# StairLed.net
KiCad netlist of a schematic drawn in Altium Designer
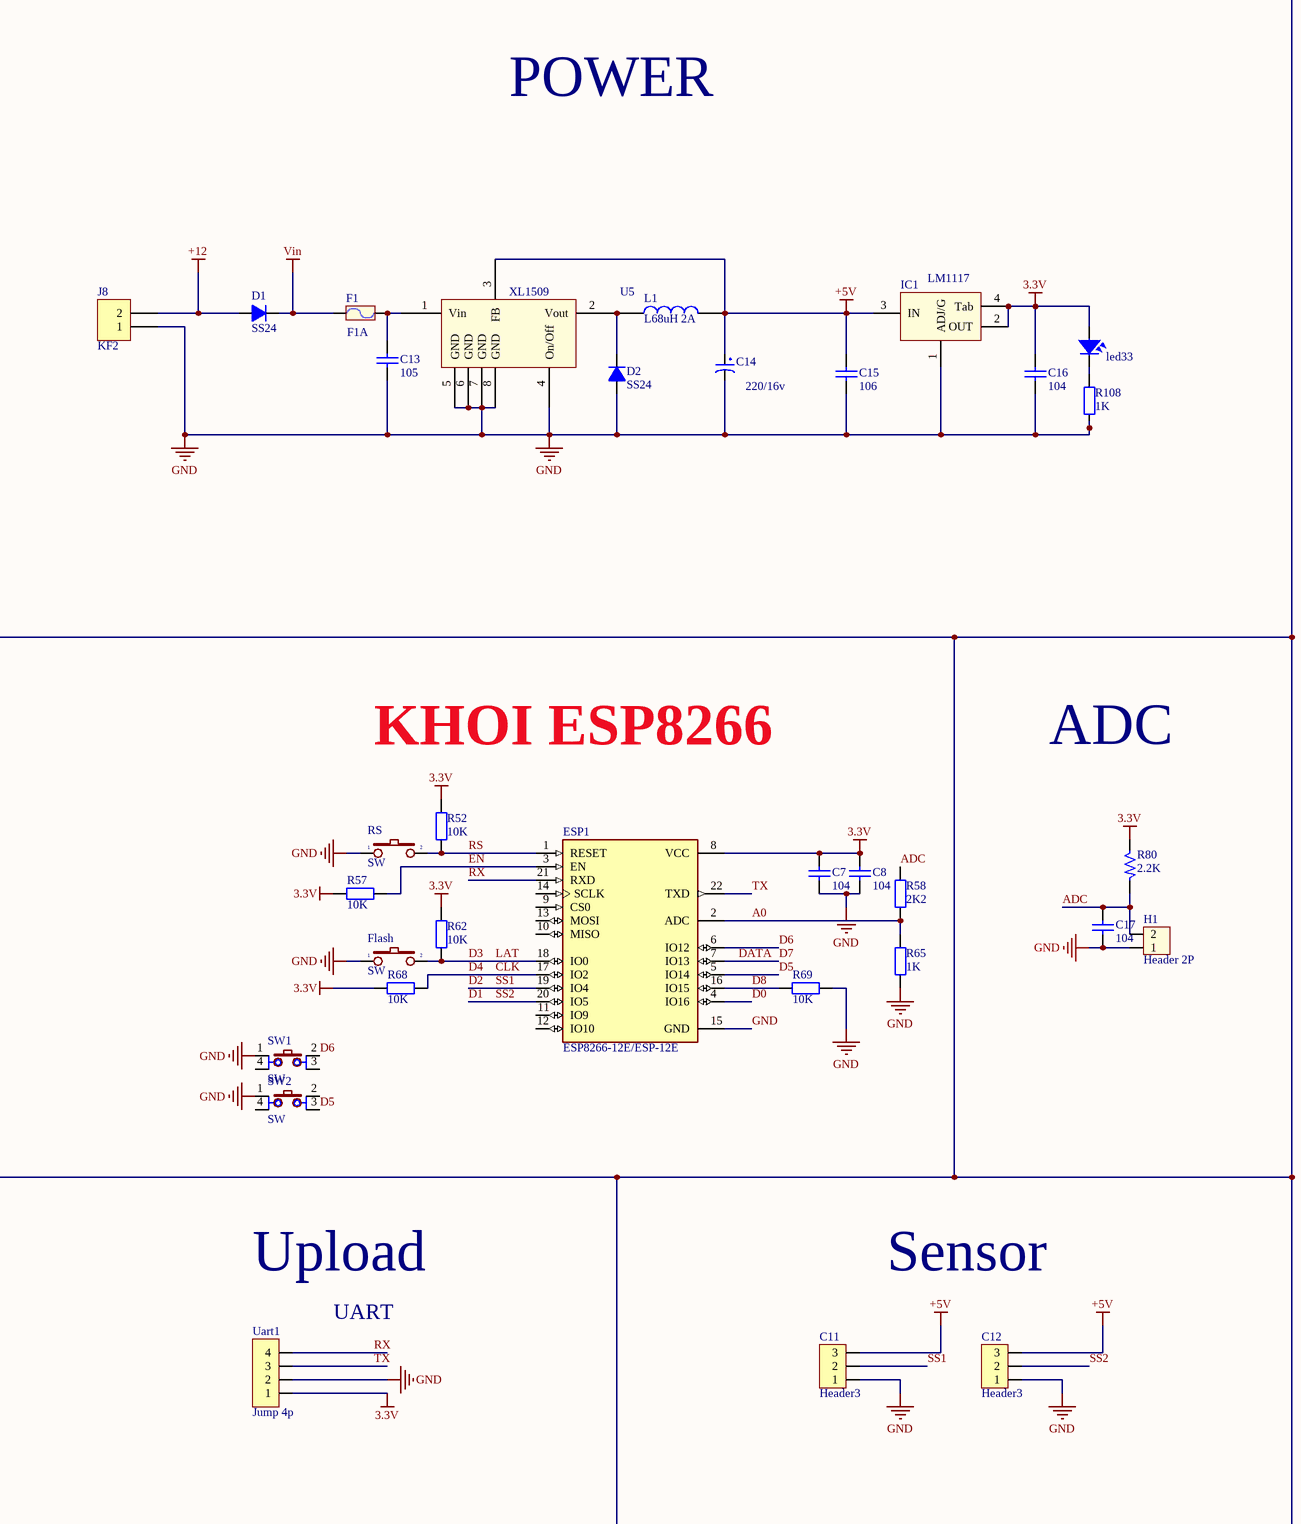
[diagram p0: StairLed.SchDoc, left]
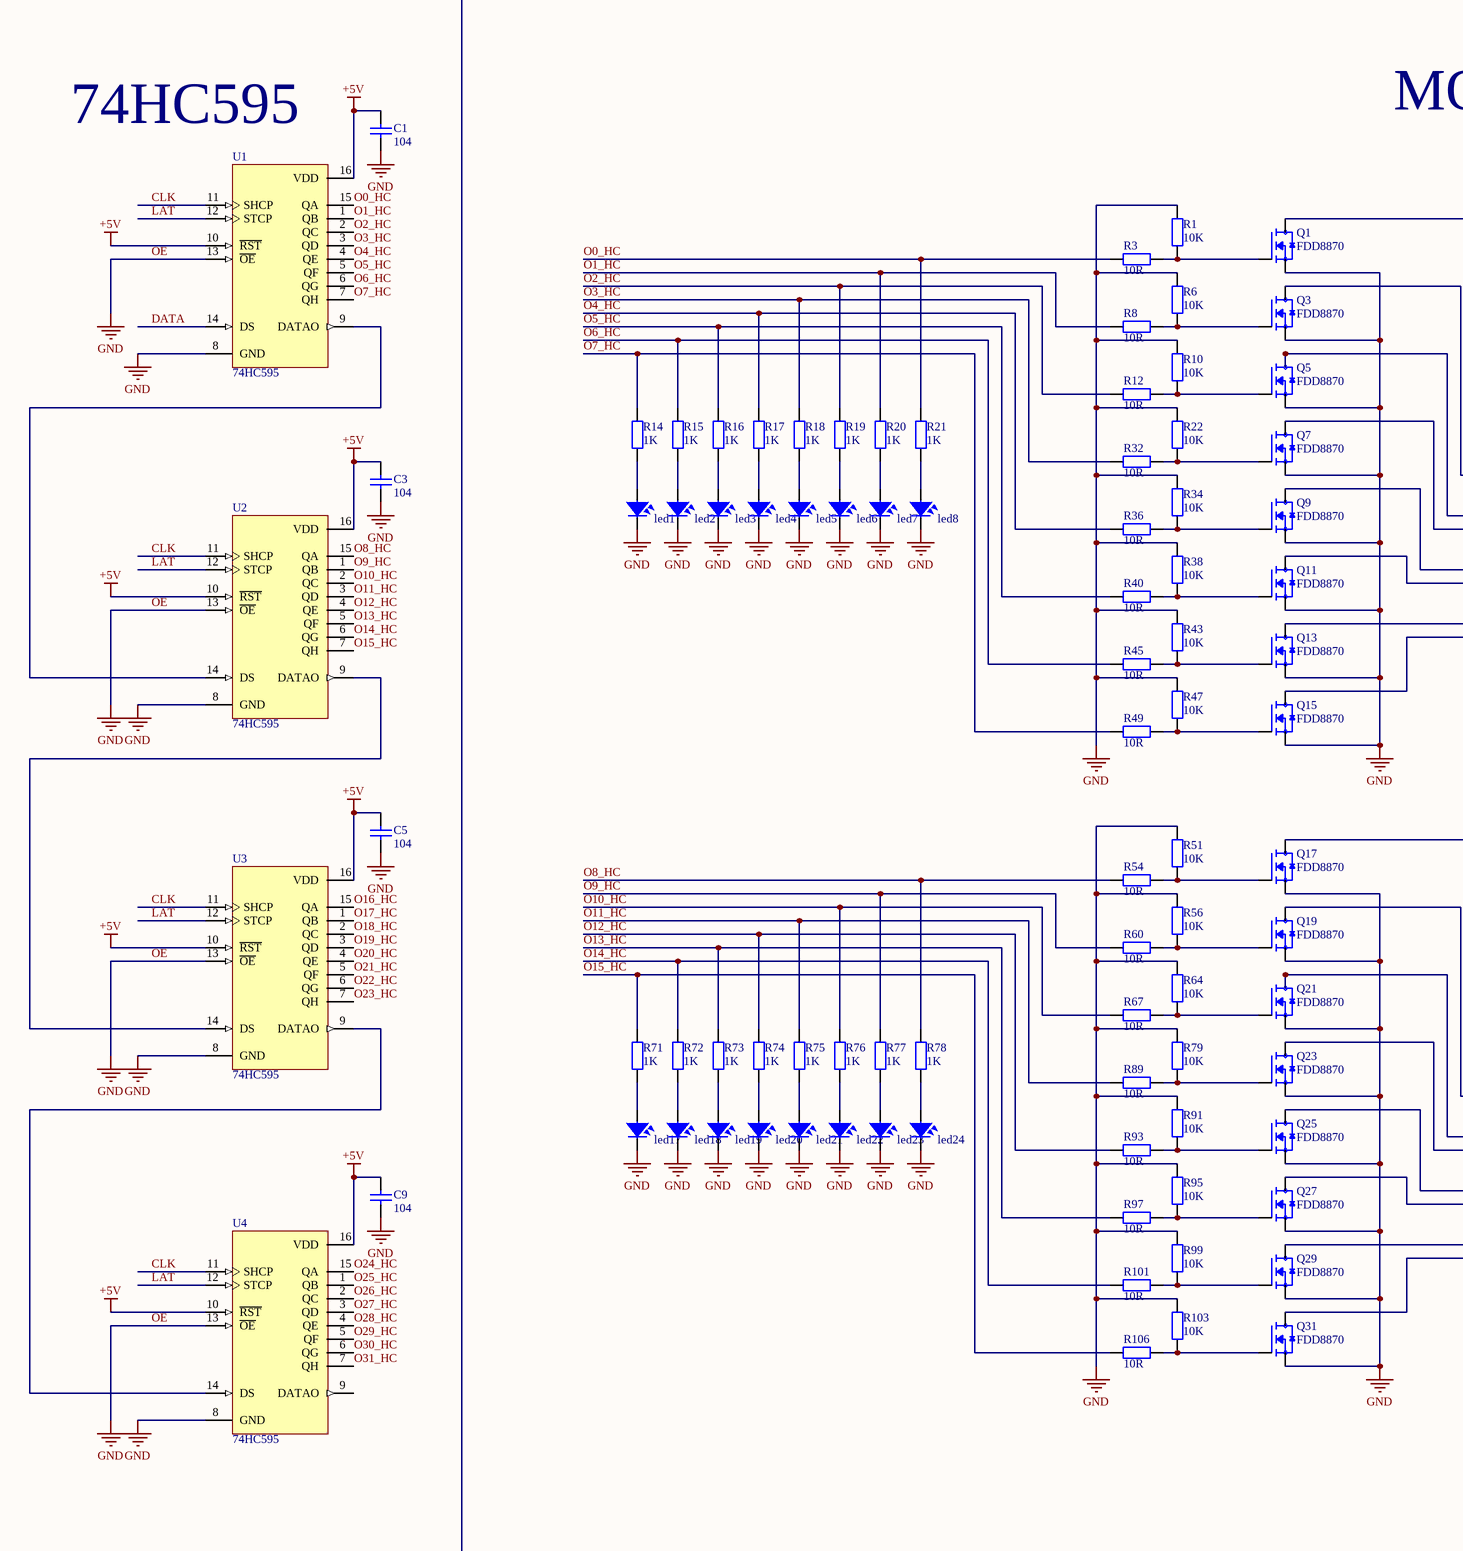
[diagram p1: StairLed.SchDoc, middle]
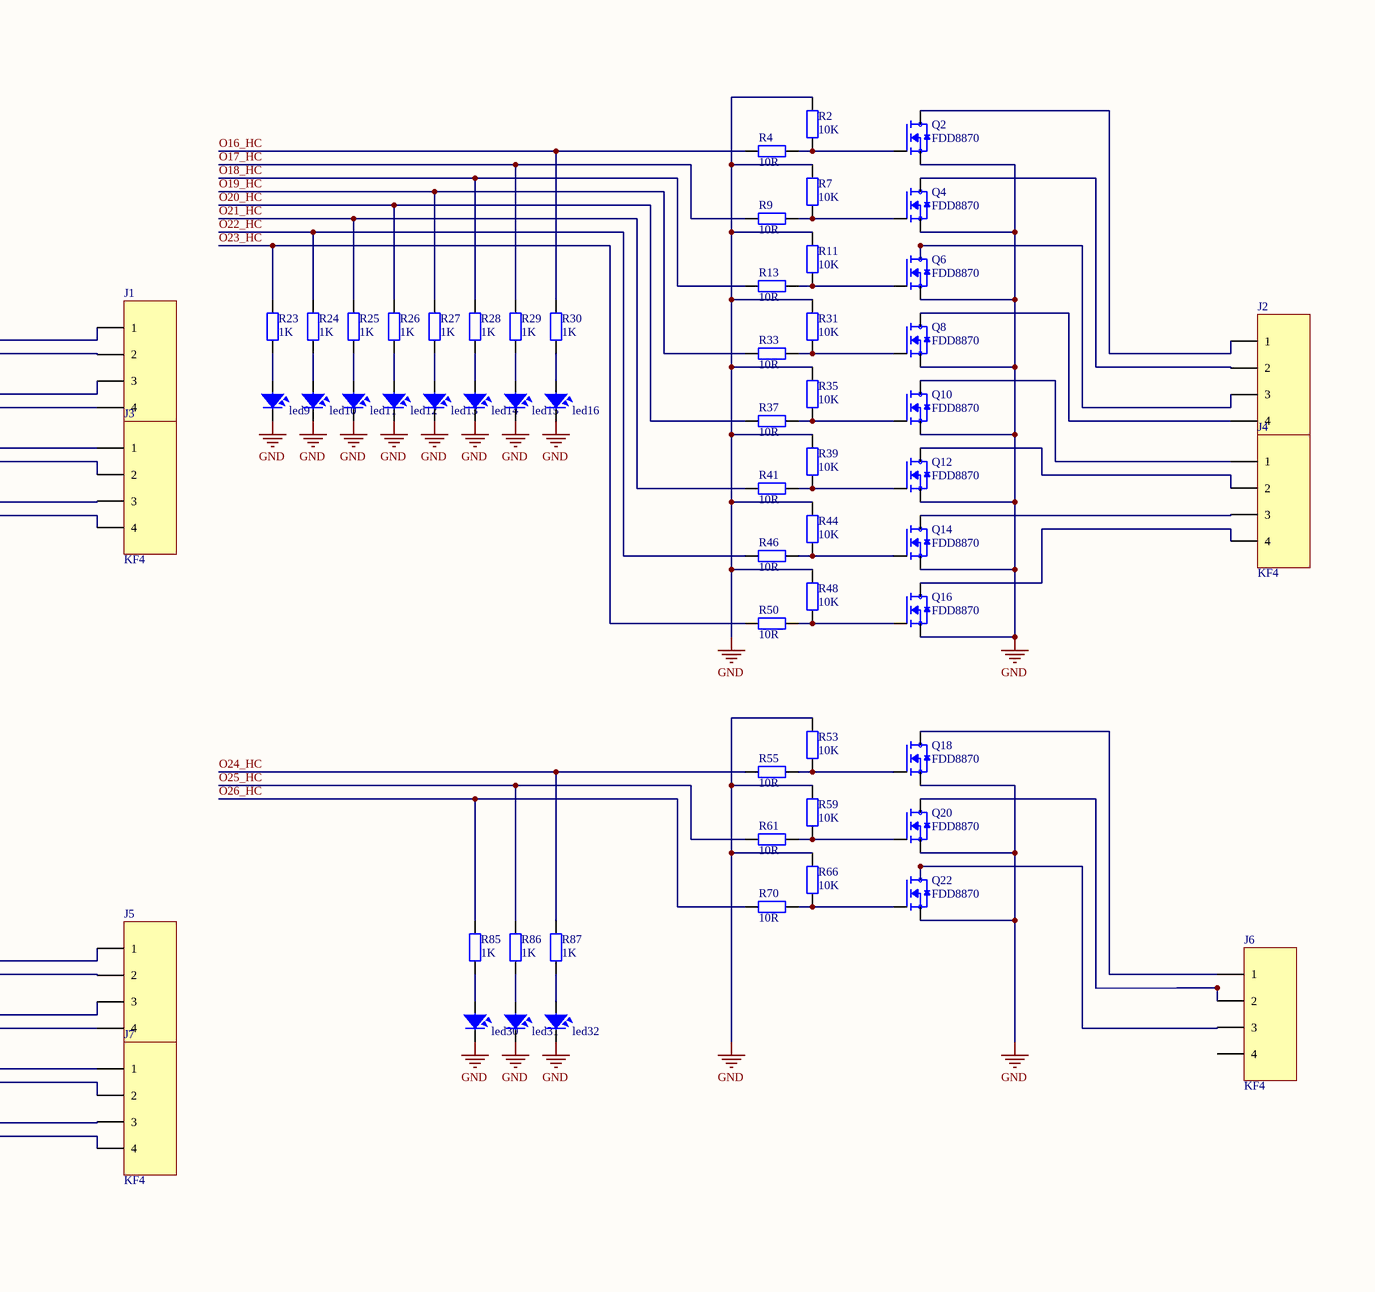
[diagram p2: StairLed.SchDoc, right]

(export (version "E")
  (design (tool "Eeschema 10.0.6"))
  (components
    (comp (ref "C1")
      (value "104")
      (footprint "Cap-0805")
      (libsource (lib "TDX_Local_LIbrary") (part "Cap-0805"))
    )
    (comp (ref "C3")
      (value "104")
      (footprint "Cap-0805")
      (libsource (lib "TDX_Local_LIbrary") (part "Cap-0805"))
    )
    (comp (ref "C5")
      (value "104")
      (footprint "Cap-0805")
      (libsource (lib "TDX_Local_LIbrary") (part "Cap-0805"))
    )
    (comp (ref "C7")
      (value "104")
      (footprint "Cap-0805")
      (description "Capacitor")
      (fields (field (name "PUBLISHER") "Altium Limited"))
      (libsource (lib "*") (part "Cap"))
    )
    (comp (ref "C8")
      (value "104")
      (footprint "Cap-0805")
      (description "Capacitor")
      (fields (field (name "PUBLISHER") "Altium Limited"))
      (libsource (lib "*") (part "Cap"))
    )
    (comp (ref "C9")
      (value "104")
      (footprint "Cap-0805")
      (libsource (lib "TDX_Local_LIbrary") (part "Cap-0805"))
    )
    (comp (ref "C11")
      (value "Header3")
      (footprint "Header3")
      (description "Header IDC, 3 x 1 Pin Vertical 2.54mm Pitch (Non-Boxed, Male)")
      (fields
        (field (name "MANUFACTURER") "Würth Elektronik eiSos GmbH")
        (field (name "PARTNO") "613002143121")
        (field (name "CREATED BY") "Karrer Zheng")
      )
      (libsource (lib "TechMT.VN_Lib_Project v2") (part "Header3"))
    )
    (comp (ref "C12")
      (value "Header3")
      (footprint "Header3")
      (description "Header IDC, 3 x 1 Pin Vertical 2.54mm Pitch (Non-Boxed, Male)")
      (fields
        (field (name "MANUFACTURER") "Würth Elektronik eiSos GmbH")
        (field (name "PARTNO") "613002143121")
        (field (name "CREATED BY") "Karrer Zheng")
      )
      (libsource (lib "TechMT.VN_Lib_Project v2") (part "Header3"))
    )
    (comp (ref "C13")
      (value "105")
      (footprint "Cap-0805")
      (description "Capacitor")
      (fields (field (name "PUBLISHER") "Altium Limited"))
      (libsource (lib "*") (part "Cap"))
    )
    (comp (ref "C14")
      (value "220/16v")
      (footprint "CAP-ALU-SMD-6.3x7.7x2.2")
      (description "T? Nhôm 330uF 50V 10x10.5MM")
      (libsource (lib "thuvien") (part "CP4"))
    )
    (comp (ref "C15")
      (value "106")
      (footprint "Cap-0805")
      (description "Capacitor")
      (fields (field (name "PUBLISHER") "Altium Limited"))
      (libsource (lib "*") (part "Cap"))
    )
    (comp (ref "C16")
      (value "104")
      (footprint "Cap-0805")
      (description "Capacitor")
      (fields (field (name "PUBLISHER") "Altium Limited"))
      (libsource (lib "*") (part "Cap"))
    )
    (comp (ref "C17")
      (value "104")
      (footprint "Cap-0805")
      (libsource (lib "TDX_Local_LIbrary") (part "Cap-0805"))
    )
    (comp (ref "D1")
      (value "SS24")
      (footprint "DO-214AC-Zenner")
      (description "Diode 1A")
      (libsource (lib "thuvien") (part "D1A"))
    )
    (comp (ref "D2")
      (value "SS24")
      (footprint "DO-214AC-Zenner")
      (description "Diode 1A")
      (libsource (lib "thuvien") (part "D1A"))
    )
    (comp (ref "ESP1")
      (value "ESP8266-12E/ESP-12E")
      (footprint "XCVR_ESP8266-12E/ESP-12E")
      (fields (field (name "MF") "AI-Thinker"))
      (libsource (lib "ESP8266-12E_ESP-12E (1)") (part "ESP8266-12E/ESP-12E"))
    )
    (comp (ref "F1")
      (value "F1A")
      (footprint "1812")
      (description "C?u chì t? ph?c h?i 1812 0.5A 30V MSMD050-30V")
      (fields (field (name "DESIGNED BY") "VanDungEvn"))
      (libsource (lib "syhaunguyen") (part "Fuse"))
    )
    (comp (ref "Flash")
      (value "SW")
      (footprint "SW1-SMD")
      (description "Switch button 2 pin")
      (libsource (lib "TechMT.VN_Lib_Project v2") (part "SW2"))
    )
    (comp (ref "H1")
      (value "Header 2P")
      (footprint "Header 2P-T")
      (libsource (lib "TDX_Local_LIbrary") (part "Header 2P"))
    )
    (comp (ref "IC1")
      (value "LM1117")
      (footprint "SOT223-4N")
      (description "AMS1117-3.3V SOT223")
      (libsource (lib "thuvien") (part "LM1117"))
    )
    (comp (ref "J1")
      (value "KF4")
      (footprint "KF4-5.08")
      (fields
        (field (name "MANUFACTURER") "Würth Elektronik eiSos GmbH")
        (field (name "PARTNO") "691133710004")
        (field (name "CREATED BY") "Baojun Chen")
      )
      (libsource (lib "TechMT.VN_Lib_Project v2") (part "KF4"))
    )
    (comp (ref "J2")
      (value "KF4")
      (footprint "KF4-5.08")
      (fields
        (field (name "MANUFACTURER") "Würth Elektronik eiSos GmbH")
        (field (name "PARTNO") "691133710004")
        (field (name "CREATED BY") "Baojun Chen")
      )
      (libsource (lib "TechMT.VN_Lib_Project v2") (part "KF4"))
    )
    (comp (ref "J3")
      (value "KF4")
      (footprint "KF4-5.08")
      (fields
        (field (name "MANUFACTURER") "Würth Elektronik eiSos GmbH")
        (field (name "PARTNO") "691133710004")
        (field (name "CREATED BY") "Baojun Chen")
      )
      (libsource (lib "TechMT.VN_Lib_Project v2") (part "KF4"))
    )
    (comp (ref "J4")
      (value "KF4")
      (footprint "KF4-5.08")
      (fields
        (field (name "MANUFACTURER") "Würth Elektronik eiSos GmbH")
        (field (name "PARTNO") "691133710004")
        (field (name "CREATED BY") "Baojun Chen")
      )
      (libsource (lib "TechMT.VN_Lib_Project v2") (part "KF4"))
    )
    (comp (ref "J5")
      (value "KF4")
      (footprint "KF4-5.08")
      (fields
        (field (name "MANUFACTURER") "Würth Elektronik eiSos GmbH")
        (field (name "PARTNO") "691133710004")
        (field (name "CREATED BY") "Baojun Chen")
      )
      (libsource (lib "TechMT.VN_Lib_Project v2") (part "KF4"))
    )
    (comp (ref "J6")
      (value "KF4")
      (footprint "KF4-5.08")
      (fields
        (field (name "MANUFACTURER") "Würth Elektronik eiSos GmbH")
        (field (name "PARTNO") "691133710004")
        (field (name "CREATED BY") "Baojun Chen")
      )
      (libsource (lib "TechMT.VN_Lib_Project v2") (part "KF4"))
    )
    (comp (ref "J7")
      (value "KF4")
      (footprint "KF4-5.08")
      (fields
        (field (name "MANUFACTURER") "Würth Elektronik eiSos GmbH")
        (field (name "PARTNO") "691133710004")
        (field (name "CREATED BY") "Baojun Chen")
      )
      (libsource (lib "TechMT.VN_Lib_Project v2") (part "KF4"))
    )
    (comp (ref "J8")
      (value "KF2")
      (footprint "KF2-5.08")
      (fields
        (field (name "MANUFACTURER") "Würth Elektronik eiSos GmbH")
        (field (name "PARTNO") "691103110002")
        (field (name "CREATED BY") "Karrer Zheng")
      )
      (libsource (lib "TechMT.VN_Lib_Project v2") (part "KF2"))
    )
    (comp (ref "L1")
      (value "L68uH 2A")
      (footprint "5D28")
      (description "Cu?n c?m dán CD74 68uH 7.4x7.4x4mm")
      (libsource (lib "*") (part "INDUCTOR"))
    )
    (comp (ref "led1")
      (value "LED SMD")
      (footprint "SM-LED-0805-Blue")
      (libsource (lib "syhaunguyen") (part "LED-SMD-0805"))
    )
    (comp (ref "led2")
      (value "LED SMD")
      (footprint "SM-LED-0805-Blue")
      (libsource (lib "syhaunguyen") (part "LED-SMD-0805"))
    )
    (comp (ref "led3")
      (value "LED SMD")
      (footprint "SM-LED-0805-Blue")
      (libsource (lib "syhaunguyen") (part "LED-SMD-0805"))
    )
    (comp (ref "led4")
      (value "LED SMD")
      (footprint "SM-LED-0805-Blue")
      (libsource (lib "syhaunguyen") (part "LED-SMD-0805"))
    )
    (comp (ref "led5")
      (value "LED SMD")
      (footprint "SM-LED-0805-Blue")
      (libsource (lib "syhaunguyen") (part "LED-SMD-0805"))
    )
    (comp (ref "led6")
      (value "LED SMD")
      (footprint "SM-LED-0805-Blue")
      (libsource (lib "syhaunguyen") (part "LED-SMD-0805"))
    )
    (comp (ref "led7")
      (value "LED SMD")
      (footprint "SM-LED-0805-Blue")
      (libsource (lib "syhaunguyen") (part "LED-SMD-0805"))
    )
    (comp (ref "led8")
      (value "LED SMD")
      (footprint "SM-LED-0805-Blue")
      (libsource (lib "syhaunguyen") (part "LED-SMD-0805"))
    )
    (comp (ref "led9")
      (value "LED SMD")
      (footprint "SM-LED-0805-Blue")
      (libsource (lib "syhaunguyen") (part "LED-SMD-0805"))
    )
    (comp (ref "led10")
      (value "LED SMD")
      (footprint "SM-LED-0805-Blue")
      (libsource (lib "syhaunguyen") (part "LED-SMD-0805"))
    )
    (comp (ref "led11")
      (value "LED SMD")
      (footprint "SM-LED-0805-Blue")
      (libsource (lib "syhaunguyen") (part "LED-SMD-0805"))
    )
    (comp (ref "led12")
      (value "LED SMD")
      (footprint "SM-LED-0805-Blue")
      (libsource (lib "syhaunguyen") (part "LED-SMD-0805"))
    )
    (comp (ref "led13")
      (value "LED SMD")
      (footprint "SM-LED-0805-Blue")
      (libsource (lib "syhaunguyen") (part "LED-SMD-0805"))
    )
    (comp (ref "led14")
      (value "LED SMD")
      (footprint "SM-LED-0805-Blue")
      (libsource (lib "syhaunguyen") (part "LED-SMD-0805"))
    )
    (comp (ref "led15")
      (value "LED SMD")
      (footprint "SM-LED-0805-Blue")
      (libsource (lib "syhaunguyen") (part "LED-SMD-0805"))
    )
    (comp (ref "led16")
      (value "LED SMD")
      (footprint "SM-LED-0805-Blue")
      (libsource (lib "syhaunguyen") (part "LED-SMD-0805"))
    )
    (comp (ref "led17")
      (value "LED SMD")
      (footprint "SM-LED-0805-Blue")
      (libsource (lib "syhaunguyen") (part "LED-SMD-0805"))
    )
    (comp (ref "led18")
      (value "LED SMD")
      (footprint "SM-LED-0805-Blue")
      (libsource (lib "syhaunguyen") (part "LED-SMD-0805"))
    )
    (comp (ref "led19")
      (value "LED SMD")
      (footprint "SM-LED-0805-Blue")
      (libsource (lib "syhaunguyen") (part "LED-SMD-0805"))
    )
    (comp (ref "led20")
      (value "LED SMD")
      (footprint "SM-LED-0805-Blue")
      (libsource (lib "syhaunguyen") (part "LED-SMD-0805"))
    )
    (comp (ref "led21")
      (value "LED SMD")
      (footprint "SM-LED-0805-Blue")
      (libsource (lib "syhaunguyen") (part "LED-SMD-0805"))
    )
    (comp (ref "led22")
      (value "LED SMD")
      (footprint "SM-LED-0805-Blue")
      (libsource (lib "syhaunguyen") (part "LED-SMD-0805"))
    )
    (comp (ref "led23")
      (value "LED SMD")
      (footprint "SM-LED-0805-Blue")
      (libsource (lib "syhaunguyen") (part "LED-SMD-0805"))
    )
    (comp (ref "led24")
      (value "LED SMD")
      (footprint "SM-LED-0805-Blue")
      (libsource (lib "syhaunguyen") (part "LED-SMD-0805"))
    )
    (comp (ref "led30")
      (value "LED SMD")
      (footprint "SM-LED-0805-Blue")
      (libsource (lib "syhaunguyen") (part "LED-SMD-0805"))
    )
    (comp (ref "led31")
      (value "LED SMD")
      (footprint "SM-LED-0805-Blue")
      (libsource (lib "syhaunguyen") (part "LED-SMD-0805"))
    )
    (comp (ref "led32")
      (value "LED SMD")
      (footprint "SM-LED-0805-Blue")
      (libsource (lib "syhaunguyen") (part "LED-SMD-0805"))
    )
    (comp (ref "led33")
      (value "LED SMD")
      (footprint "SM-LED-0805-Blue")
      (libsource (lib "syhaunguyen") (part "LED-SMD-0805"))
    )
    (comp (ref "Q1")
      (value "FDD8870")
      (footprint "TRANS_SQD50N03-06P-GE3")
      (fields (field (name "MP") "SQD50N03-06P-GE3"))
      (libsource (lib "SQD50N03-06P-GE3") (part "SQD50N03-06P-GE3"))
    )
    (comp (ref "Q2")
      (value "FDD8870")
      (footprint "TRANS_SQD50N03-06P-GE3")
      (fields (field (name "MP") "SQD50N03-06P-GE3"))
      (libsource (lib "SQD50N03-06P-GE3") (part "SQD50N03-06P-GE3"))
    )
    (comp (ref "Q3")
      (value "FDD8870")
      (footprint "TRANS_SQD50N03-06P-GE3")
      (fields (field (name "MP") "SQD50N03-06P-GE3"))
      (libsource (lib "SQD50N03-06P-GE3") (part "SQD50N03-06P-GE3"))
    )
    (comp (ref "Q4")
      (value "FDD8870")
      (footprint "TRANS_SQD50N03-06P-GE3")
      (fields (field (name "MP") "SQD50N03-06P-GE3"))
      (libsource (lib "SQD50N03-06P-GE3") (part "SQD50N03-06P-GE3"))
    )
    (comp (ref "Q5")
      (value "FDD8870")
      (footprint "TRANS_SQD50N03-06P-GE3")
      (fields (field (name "MP") "SQD50N03-06P-GE3"))
      (libsource (lib "SQD50N03-06P-GE3") (part "SQD50N03-06P-GE3"))
    )
    (comp (ref "Q6")
      (value "FDD8870")
      (footprint "TRANS_SQD50N03-06P-GE3")
      (fields (field (name "MP") "SQD50N03-06P-GE3"))
      (libsource (lib "SQD50N03-06P-GE3") (part "SQD50N03-06P-GE3"))
    )
    (comp (ref "Q7")
      (value "FDD8870")
      (footprint "TRANS_SQD50N03-06P-GE3")
      (fields (field (name "MP") "SQD50N03-06P-GE3"))
      (libsource (lib "SQD50N03-06P-GE3") (part "SQD50N03-06P-GE3"))
    )
    (comp (ref "Q8")
      (value "FDD8870")
      (footprint "TRANS_SQD50N03-06P-GE3")
      (fields (field (name "MP") "SQD50N03-06P-GE3"))
      (libsource (lib "SQD50N03-06P-GE3") (part "SQD50N03-06P-GE3"))
    )
    (comp (ref "Q9")
      (value "FDD8870")
      (footprint "TRANS_SQD50N03-06P-GE3")
      (fields (field (name "MP") "SQD50N03-06P-GE3"))
      (libsource (lib "SQD50N03-06P-GE3") (part "SQD50N03-06P-GE3"))
    )
    (comp (ref "Q10")
      (value "FDD8870")
      (footprint "TRANS_SQD50N03-06P-GE3")
      (fields (field (name "MP") "SQD50N03-06P-GE3"))
      (libsource (lib "SQD50N03-06P-GE3") (part "SQD50N03-06P-GE3"))
    )
    (comp (ref "Q11")
      (value "FDD8870")
      (footprint "TRANS_SQD50N03-06P-GE3")
      (fields (field (name "MP") "SQD50N03-06P-GE3"))
      (libsource (lib "SQD50N03-06P-GE3") (part "SQD50N03-06P-GE3"))
    )
    (comp (ref "Q12")
      (value "FDD8870")
      (footprint "TRANS_SQD50N03-06P-GE3")
      (fields (field (name "MP") "SQD50N03-06P-GE3"))
      (libsource (lib "SQD50N03-06P-GE3") (part "SQD50N03-06P-GE3"))
    )
    (comp (ref "Q13")
      (value "FDD8870")
      (footprint "TRANS_SQD50N03-06P-GE3")
      (fields (field (name "MP") "SQD50N03-06P-GE3"))
      (libsource (lib "SQD50N03-06P-GE3") (part "SQD50N03-06P-GE3"))
    )
    (comp (ref "Q14")
      (value "FDD8870")
      (footprint "TRANS_SQD50N03-06P-GE3")
      (fields (field (name "MP") "SQD50N03-06P-GE3"))
      (libsource (lib "SQD50N03-06P-GE3") (part "SQD50N03-06P-GE3"))
    )
    (comp (ref "Q15")
      (value "FDD8870")
      (footprint "TRANS_SQD50N03-06P-GE3")
      (fields (field (name "MP") "SQD50N03-06P-GE3"))
      (libsource (lib "SQD50N03-06P-GE3") (part "SQD50N03-06P-GE3"))
    )
    (comp (ref "Q16")
      (value "FDD8870")
      (footprint "TRANS_SQD50N03-06P-GE3")
      (fields (field (name "MP") "SQD50N03-06P-GE3"))
      (libsource (lib "SQD50N03-06P-GE3") (part "SQD50N03-06P-GE3"))
    )
    (comp (ref "Q17")
      (value "FDD8870")
      (footprint "TRANS_SQD50N03-06P-GE3")
      (fields (field (name "MP") "SQD50N03-06P-GE3"))
      (libsource (lib "SQD50N03-06P-GE3") (part "SQD50N03-06P-GE3"))
    )
    (comp (ref "Q18")
      (value "FDD8870")
      (footprint "TRANS_SQD50N03-06P-GE3")
      (fields (field (name "MP") "SQD50N03-06P-GE3"))
      (libsource (lib "SQD50N03-06P-GE3") (part "SQD50N03-06P-GE3"))
    )
    (comp (ref "Q19")
      (value "FDD8870")
      (footprint "TRANS_SQD50N03-06P-GE3")
      (fields (field (name "MP") "SQD50N03-06P-GE3"))
      (libsource (lib "SQD50N03-06P-GE3") (part "SQD50N03-06P-GE3"))
    )
    (comp (ref "Q20")
      (value "FDD8870")
      (footprint "TRANS_SQD50N03-06P-GE3")
      (fields (field (name "MP") "SQD50N03-06P-GE3"))
      (libsource (lib "SQD50N03-06P-GE3") (part "SQD50N03-06P-GE3"))
    )
    (comp (ref "Q21")
      (value "FDD8870")
      (footprint "TRANS_SQD50N03-06P-GE3")
      (fields (field (name "MP") "SQD50N03-06P-GE3"))
      (libsource (lib "SQD50N03-06P-GE3") (part "SQD50N03-06P-GE3"))
    )
    (comp (ref "Q22")
      (value "FDD8870")
      (footprint "TRANS_SQD50N03-06P-GE3")
      (fields (field (name "MP") "SQD50N03-06P-GE3"))
      (libsource (lib "SQD50N03-06P-GE3") (part "SQD50N03-06P-GE3"))
    )
    (comp (ref "Q23")
      (value "FDD8870")
      (footprint "TRANS_SQD50N03-06P-GE3")
      (fields (field (name "MP") "SQD50N03-06P-GE3"))
      (libsource (lib "SQD50N03-06P-GE3") (part "SQD50N03-06P-GE3"))
    )
    (comp (ref "Q25")
      (value "FDD8870")
      (footprint "TRANS_SQD50N03-06P-GE3")
      (fields (field (name "MP") "SQD50N03-06P-GE3"))
      (libsource (lib "SQD50N03-06P-GE3") (part "SQD50N03-06P-GE3"))
    )
    (comp (ref "Q27")
      (value "FDD8870")
      (footprint "TRANS_SQD50N03-06P-GE3")
      (fields (field (name "MP") "SQD50N03-06P-GE3"))
      (libsource (lib "SQD50N03-06P-GE3") (part "SQD50N03-06P-GE3"))
    )
    (comp (ref "Q29")
      (value "FDD8870")
      (footprint "TRANS_SQD50N03-06P-GE3")
      (fields (field (name "MP") "SQD50N03-06P-GE3"))
      (libsource (lib "SQD50N03-06P-GE3") (part "SQD50N03-06P-GE3"))
    )
    (comp (ref "Q31")
      (value "FDD8870")
      (footprint "TRANS_SQD50N03-06P-GE3")
      (fields (field (name "MP") "SQD50N03-06P-GE3"))
      (libsource (lib "SQD50N03-06P-GE3") (part "SQD50N03-06P-GE3"))
    )
    (comp (ref "R1")
      (value "10K")
      (footprint "R0805")
      (description "Tr? 0805 1%")
      (fields (field (name "PUBLISHER") "Altium Limited"))
      (libsource (lib "") (part "RES_08_2"))
    )
    (comp (ref "R2")
      (value "10K")
      (footprint "R0805")
      (description "Tr? 0805 1%")
      (fields (field (name "PUBLISHER") "Altium Limited"))
      (libsource (lib "") (part "RES_08_2"))
    )
    (comp (ref "R3")
      (value "10R")
      (footprint "R0805")
      (description "Tr? 0805 1%")
      (fields (field (name "PUBLISHER") "Altium Limited"))
      (libsource (lib "") (part "RES_08_1"))
    )
    (comp (ref "R4")
      (value "10R")
      (footprint "R0805")
      (description "Tr? 0805 1%")
      (fields (field (name "PUBLISHER") "Altium Limited"))
      (libsource (lib "") (part "RES_08_1"))
    )
    (comp (ref "R6")
      (value "10K")
      (footprint "R0805")
      (description "Tr? 0805 1%")
      (fields (field (name "PUBLISHER") "Altium Limited"))
      (libsource (lib "") (part "RES_08_2"))
    )
    (comp (ref "R7")
      (value "10K")
      (footprint "R0805")
      (description "Tr? 0805 1%")
      (fields (field (name "PUBLISHER") "Altium Limited"))
      (libsource (lib "") (part "RES_08_2"))
    )
    (comp (ref "R8")
      (value "10R")
      (footprint "R0805")
      (description "Tr? 0805 1%")
      (fields (field (name "PUBLISHER") "Altium Limited"))
      (libsource (lib "") (part "RES_08_1"))
    )
    (comp (ref "R9")
      (value "10R")
      (footprint "R0805")
      (description "Tr? 0805 1%")
      (fields (field (name "PUBLISHER") "Altium Limited"))
      (libsource (lib "") (part "RES_08_1"))
    )
    (comp (ref "R10")
      (value "10K")
      (footprint "R0805")
      (description "Tr? 0805 1%")
      (fields (field (name "PUBLISHER") "Altium Limited"))
      (libsource (lib "") (part "RES_08_2"))
    )
    (comp (ref "R11")
      (value "10K")
      (footprint "R0805")
      (description "Tr? 0805 1%")
      (fields (field (name "PUBLISHER") "Altium Limited"))
      (libsource (lib "") (part "RES_08_2"))
    )
    (comp (ref "R12")
      (value "10R")
      (footprint "R0805")
      (description "Tr? 0805 1%")
      (fields (field (name "PUBLISHER") "Altium Limited"))
      (libsource (lib "") (part "RES_08_1"))
    )
    (comp (ref "R13")
      (value "10R")
      (footprint "R0805")
      (description "Tr? 0805 1%")
      (fields (field (name "PUBLISHER") "Altium Limited"))
      (libsource (lib "") (part "RES_08_1"))
    )
    (comp (ref "R14")
      (value "1K")
      (footprint "R0805")
      (description "Tr? 0805 1%")
      (fields (field (name "PUBLISHER") "Altium Limited"))
      (libsource (lib "Schematic") (part "RES_08"))
    )
    (comp (ref "R15")
      (value "1K")
      (footprint "R0805")
      (description "Tr? 0805 1%")
      (fields (field (name "PUBLISHER") "Altium Limited"))
      (libsource (lib "Schematic") (part "RES_08"))
    )
    (comp (ref "R16")
      (value "1K")
      (footprint "R0805")
      (description "Tr? 0805 1%")
      (fields (field (name "PUBLISHER") "Altium Limited"))
      (libsource (lib "Schematic") (part "RES_08"))
    )
    (comp (ref "R17")
      (value "1K")
      (footprint "R0805")
      (description "Tr? 0805 1%")
      (fields (field (name "PUBLISHER") "Altium Limited"))
      (libsource (lib "Schematic") (part "RES_08"))
    )
    (comp (ref "R18")
      (value "1K")
      (footprint "R0805")
      (description "Tr? 0805 1%")
      (fields (field (name "PUBLISHER") "Altium Limited"))
      (libsource (lib "Schematic") (part "RES_08"))
    )
    (comp (ref "R19")
      (value "1K")
      (footprint "R0805")
      (description "Tr? 0805 1%")
      (fields (field (name "PUBLISHER") "Altium Limited"))
      (libsource (lib "Schematic") (part "RES_08"))
    )
    (comp (ref "R20")
      (value "1K")
      (footprint "R0805")
      (description "Tr? 0805 1%")
      (fields (field (name "PUBLISHER") "Altium Limited"))
      (libsource (lib "Schematic") (part "RES_08"))
    )
    (comp (ref "R21")
      (value "1K")
      (footprint "R0805")
      (description "Tr? 0805 1%")
      (fields (field (name "PUBLISHER") "Altium Limited"))
      (libsource (lib "Schematic") (part "RES_08"))
    )
    (comp (ref "R22")
      (value "10K")
      (footprint "R0805")
      (description "Tr? 0805 1%")
      (fields (field (name "PUBLISHER") "Altium Limited"))
      (libsource (lib "") (part "RES_08_2"))
    )
    (comp (ref "R23")
      (value "1K")
      (footprint "R0805")
      (description "Tr? 0805 1%")
      (fields (field (name "PUBLISHER") "Altium Limited"))
      (libsource (lib "Schematic") (part "RES_08"))
    )
    (comp (ref "R24")
      (value "1K")
      (footprint "R0805")
      (description "Tr? 0805 1%")
      (fields (field (name "PUBLISHER") "Altium Limited"))
      (libsource (lib "Schematic") (part "RES_08"))
    )
    (comp (ref "R25")
      (value "1K")
      (footprint "R0805")
      (description "Tr? 0805 1%")
      (fields (field (name "PUBLISHER") "Altium Limited"))
      (libsource (lib "Schematic") (part "RES_08"))
    )
    (comp (ref "R26")
      (value "1K")
      (footprint "R0805")
      (description "Tr? 0805 1%")
      (fields (field (name "PUBLISHER") "Altium Limited"))
      (libsource (lib "Schematic") (part "RES_08"))
    )
    (comp (ref "R27")
      (value "1K")
      (footprint "R0805")
      (description "Tr? 0805 1%")
      (fields (field (name "PUBLISHER") "Altium Limited"))
      (libsource (lib "Schematic") (part "RES_08"))
    )
    (comp (ref "R28")
      (value "1K")
      (footprint "R0805")
      (description "Tr? 0805 1%")
      (fields (field (name "PUBLISHER") "Altium Limited"))
      (libsource (lib "Schematic") (part "RES_08"))
    )
    (comp (ref "R29")
      (value "1K")
      (footprint "R0805")
      (description "Tr? 0805 1%")
      (fields (field (name "PUBLISHER") "Altium Limited"))
      (libsource (lib "Schematic") (part "RES_08"))
    )
    (comp (ref "R30")
      (value "1K")
      (footprint "R0805")
      (description "Tr? 0805 1%")
      (fields (field (name "PUBLISHER") "Altium Limited"))
      (libsource (lib "Schematic") (part "RES_08"))
    )
    (comp (ref "R31")
      (value "10K")
      (footprint "R0805")
      (description "Tr? 0805 1%")
      (fields (field (name "PUBLISHER") "Altium Limited"))
      (libsource (lib "") (part "RES_08_2"))
    )
    (comp (ref "R32")
      (value "10R")
      (footprint "R0805")
      (description "Tr? 0805 1%")
      (fields (field (name "PUBLISHER") "Altium Limited"))
      (libsource (lib "") (part "RES_08_1"))
    )
    (comp (ref "R33")
      (value "10R")
      (footprint "R0805")
      (description "Tr? 0805 1%")
      (fields (field (name "PUBLISHER") "Altium Limited"))
      (libsource (lib "") (part "RES_08_1"))
    )
    (comp (ref "R34")
      (value "10K")
      (footprint "R0805")
      (description "Tr? 0805 1%")
      (fields (field (name "PUBLISHER") "Altium Limited"))
      (libsource (lib "") (part "RES_08_2"))
    )
    (comp (ref "R35")
      (value "10K")
      (footprint "R0805")
      (description "Tr? 0805 1%")
      (fields (field (name "PUBLISHER") "Altium Limited"))
      (libsource (lib "") (part "RES_08_2"))
    )
    (comp (ref "R36")
      (value "10R")
      (footprint "R0805")
      (description "Tr? 0805 1%")
      (fields (field (name "PUBLISHER") "Altium Limited"))
      (libsource (lib "") (part "RES_08_1"))
    )
    (comp (ref "R37")
      (value "10R")
      (footprint "R0805")
      (description "Tr? 0805 1%")
      (fields (field (name "PUBLISHER") "Altium Limited"))
      (libsource (lib "") (part "RES_08_1"))
    )
    (comp (ref "R38")
      (value "10K")
      (footprint "R0805")
      (description "Tr? 0805 1%")
      (fields (field (name "PUBLISHER") "Altium Limited"))
      (libsource (lib "") (part "RES_08_2"))
    )
    (comp (ref "R39")
      (value "10K")
      (footprint "R0805")
      (description "Tr? 0805 1%")
      (fields (field (name "PUBLISHER") "Altium Limited"))
      (libsource (lib "") (part "RES_08_2"))
    )
    (comp (ref "R40")
      (value "10R")
      (footprint "R0805")
      (description "Tr? 0805 1%")
      (fields (field (name "PUBLISHER") "Altium Limited"))
      (libsource (lib "") (part "RES_08_1"))
    )
    (comp (ref "R41")
      (value "10R")
      (footprint "R0805")
      (description "Tr? 0805 1%")
      (fields (field (name "PUBLISHER") "Altium Limited"))
      (libsource (lib "") (part "RES_08_1"))
    )
    (comp (ref "R43")
      (value "10K")
      (footprint "R0805")
      (description "Tr? 0805 1%")
      (fields (field (name "PUBLISHER") "Altium Limited"))
      (libsource (lib "") (part "RES_08_2"))
    )
    (comp (ref "R44")
      (value "10K")
      (footprint "R0805")
      (description "Tr? 0805 1%")
      (fields (field (name "PUBLISHER") "Altium Limited"))
      (libsource (lib "") (part "RES_08_2"))
    )
    (comp (ref "R45")
      (value "10R")
      (footprint "R0805")
      (description "Tr? 0805 1%")
      (fields (field (name "PUBLISHER") "Altium Limited"))
      (libsource (lib "") (part "RES_08_1"))
    )
    (comp (ref "R46")
      (value "10R")
      (footprint "R0805")
      (description "Tr? 0805 1%")
      (fields (field (name "PUBLISHER") "Altium Limited"))
      (libsource (lib "") (part "RES_08_1"))
    )
    (comp (ref "R47")
      (value "10K")
      (footprint "R0805")
      (description "Tr? 0805 1%")
      (fields (field (name "PUBLISHER") "Altium Limited"))
      (libsource (lib "") (part "RES_08_2"))
    )
    (comp (ref "R48")
      (value "10K")
      (footprint "R0805")
      (description "Tr? 0805 1%")
      (fields (field (name "PUBLISHER") "Altium Limited"))
      (libsource (lib "") (part "RES_08_2"))
    )
    (comp (ref "R49")
      (value "10R")
      (footprint "R0805")
      (description "Tr? 0805 1%")
      (fields (field (name "PUBLISHER") "Altium Limited"))
      (libsource (lib "") (part "RES_08_1"))
    )
    (comp (ref "R50")
      (value "10R")
      (footprint "R0805")
      (description "Tr? 0805 1%")
      (fields (field (name "PUBLISHER") "Altium Limited"))
      (libsource (lib "") (part "RES_08_1"))
    )
    (comp (ref "R51")
      (value "10K")
      (footprint "R0805")
      (description "Tr? 0805 1%")
      (fields (field (name "PUBLISHER") "Altium Limited"))
      (libsource (lib "") (part "RES_08_2"))
    )
    (comp (ref "R52")
      (value "10K")
      (footprint "R0805")
      (description "RES_08")
      (fields (field (name "PUBLISHER") "Altium Limited"))
      (libsource (lib "") (part "RES_08_1"))
    )
    (comp (ref "R53")
      (value "10K")
      (footprint "R0805")
      (description "Tr? 0805 1%")
      (fields (field (name "PUBLISHER") "Altium Limited"))
      (libsource (lib "") (part "RES_08_2"))
    )
    (comp (ref "R54")
      (value "10R")
      (footprint "R0805")
      (description "Tr? 0805 1%")
      (fields (field (name "PUBLISHER") "Altium Limited"))
      (libsource (lib "") (part "RES_08_1"))
    )
    (comp (ref "R55")
      (value "10R")
      (footprint "R0805")
      (description "Tr? 0805 1%")
      (fields (field (name "PUBLISHER") "Altium Limited"))
      (libsource (lib "") (part "RES_08_1"))
    )
    (comp (ref "R56")
      (value "10K")
      (footprint "R0805")
      (description "Tr? 0805 1%")
      (fields (field (name "PUBLISHER") "Altium Limited"))
      (libsource (lib "") (part "RES_08_2"))
    )
    (comp (ref "R57")
      (value "10K")
      (footprint "R0805")
      (description "RES_08")
      (fields (field (name "PUBLISHER") "Altium Limited"))
      (libsource (lib "TransmitterMainBoard") (part "RES_08"))
    )
    (comp (ref "R58")
      (value "2K2")
      (footprint "R0805")
      (description "Tr? 0805 1%")
      (fields (field (name "PUBLISHER") "Altium Limited"))
      (libsource (lib "") (part "RES_08_2"))
    )
    (comp (ref "R59")
      (value "10K")
      (footprint "R0805")
      (description "Tr? 0805 1%")
      (fields (field (name "PUBLISHER") "Altium Limited"))
      (libsource (lib "") (part "RES_08_2"))
    )
    (comp (ref "R60")
      (value "10R")
      (footprint "R0805")
      (description "Tr? 0805 1%")
      (fields (field (name "PUBLISHER") "Altium Limited"))
      (libsource (lib "") (part "RES_08_1"))
    )
    (comp (ref "R61")
      (value "10R")
      (footprint "R0805")
      (description "Tr? 0805 1%")
      (fields (field (name "PUBLISHER") "Altium Limited"))
      (libsource (lib "") (part "RES_08_1"))
    )
    (comp (ref "R62")
      (value "10K")
      (footprint "R0805")
      (description "RES_08")
      (fields (field (name "PUBLISHER") "Altium Limited"))
      (libsource (lib "") (part "RES_08_1"))
    )
    (comp (ref "R64")
      (value "10K")
      (footprint "R0805")
      (description "Tr? 0805 1%")
      (fields (field (name "PUBLISHER") "Altium Limited"))
      (libsource (lib "") (part "RES_08_2"))
    )
    (comp (ref "R65")
      (value "1K")
      (footprint "R0805")
      (description "Tr? 0805 1%")
      (fields (field (name "PUBLISHER") "Altium Limited"))
      (libsource (lib "") (part "RES_08_2"))
    )
    (comp (ref "R66")
      (value "10K")
      (footprint "R0805")
      (description "Tr? 0805 1%")
      (fields (field (name "PUBLISHER") "Altium Limited"))
      (libsource (lib "") (part "RES_08_2"))
    )
    (comp (ref "R67")
      (value "10R")
      (footprint "R0805")
      (description "Tr? 0805 1%")
      (fields (field (name "PUBLISHER") "Altium Limited"))
      (libsource (lib "") (part "RES_08_1"))
    )
    (comp (ref "R68")
      (value "10K")
      (footprint "R0805")
      (description "RES_08")
      (fields (field (name "PUBLISHER") "Altium Limited"))
      (libsource (lib "TransmitterMainBoard") (part "RES_08"))
    )
    (comp (ref "R69")
      (value "10K")
      (footprint "R0805")
      (description "RES_08")
      (fields (field (name "PUBLISHER") "Altium Limited"))
      (libsource (lib "TransmitterMainBoard") (part "RES_08"))
    )
    (comp (ref "R70")
      (value "10R")
      (footprint "R0805")
      (description "Tr? 0805 1%")
      (fields (field (name "PUBLISHER") "Altium Limited"))
      (libsource (lib "") (part "RES_08_1"))
    )
    (comp (ref "R71")
      (value "1K")
      (footprint "R0805")
      (description "Tr? 0805 1%")
      (fields (field (name "PUBLISHER") "Altium Limited"))
      (libsource (lib "Schematic") (part "RES_08"))
    )
    (comp (ref "R72")
      (value "1K")
      (footprint "R0805")
      (description "Tr? 0805 1%")
      (fields (field (name "PUBLISHER") "Altium Limited"))
      (libsource (lib "Schematic") (part "RES_08"))
    )
    (comp (ref "R73")
      (value "1K")
      (footprint "R0805")
      (description "Tr? 0805 1%")
      (fields (field (name "PUBLISHER") "Altium Limited"))
      (libsource (lib "Schematic") (part "RES_08"))
    )
    (comp (ref "R74")
      (value "1K")
      (footprint "R0805")
      (description "Tr? 0805 1%")
      (fields (field (name "PUBLISHER") "Altium Limited"))
      (libsource (lib "Schematic") (part "RES_08"))
    )
    (comp (ref "R75")
      (value "1K")
      (footprint "R0805")
      (description "Tr? 0805 1%")
      (fields (field (name "PUBLISHER") "Altium Limited"))
      (libsource (lib "Schematic") (part "RES_08"))
    )
    (comp (ref "R76")
      (value "1K")
      (footprint "R0805")
      (description "Tr? 0805 1%")
      (fields (field (name "PUBLISHER") "Altium Limited"))
      (libsource (lib "Schematic") (part "RES_08"))
    )
    (comp (ref "R77")
      (value "1K")
      (footprint "R0805")
      (description "Tr? 0805 1%")
      (fields (field (name "PUBLISHER") "Altium Limited"))
      (libsource (lib "Schematic") (part "RES_08"))
    )
    (comp (ref "R78")
      (value "1K")
      (footprint "R0805")
      (description "Tr? 0805 1%")
      (fields (field (name "PUBLISHER") "Altium Limited"))
      (libsource (lib "Schematic") (part "RES_08"))
    )
    (comp (ref "R79")
      (value "10K")
      (footprint "R0805")
      (description "Tr? 0805 1%")
      (fields (field (name "PUBLISHER") "Altium Limited"))
      (libsource (lib "") (part "RES_08_2"))
    )
    (comp (ref "R80")
      (value "2.2K")
      (footprint "Res-0805")
      (libsource (lib "TDX_Local_LIbrary") (part "Res-0805"))
    )
    (comp (ref "R85")
      (value "1K")
      (footprint "R0805")
      (description "Tr? 0805 1%")
      (fields (field (name "PUBLISHER") "Altium Limited"))
      (libsource (lib "Schematic") (part "RES_08"))
    )
    (comp (ref "R86")
      (value "1K")
      (footprint "R0805")
      (description "Tr? 0805 1%")
      (fields (field (name "PUBLISHER") "Altium Limited"))
      (libsource (lib "Schematic") (part "RES_08"))
    )
    (comp (ref "R87")
      (value "1K")
      (footprint "R0805")
      (description "Tr? 0805 1%")
      (fields (field (name "PUBLISHER") "Altium Limited"))
      (libsource (lib "Schematic") (part "RES_08"))
    )
    (comp (ref "R89")
      (value "10R")
      (footprint "R0805")
      (description "Tr? 0805 1%")
      (fields (field (name "PUBLISHER") "Altium Limited"))
      (libsource (lib "") (part "RES_08_1"))
    )
    (comp (ref "R91")
      (value "10K")
      (footprint "R0805")
      (description "Tr? 0805 1%")
      (fields (field (name "PUBLISHER") "Altium Limited"))
      (libsource (lib "") (part "RES_08_2"))
    )
    (comp (ref "R93")
      (value "10R")
      (footprint "R0805")
      (description "Tr? 0805 1%")
      (fields (field (name "PUBLISHER") "Altium Limited"))
      (libsource (lib "") (part "RES_08_1"))
    )
    (comp (ref "R95")
      (value "10K")
      (footprint "R0805")
      (description "Tr? 0805 1%")
      (fields (field (name "PUBLISHER") "Altium Limited"))
      (libsource (lib "") (part "RES_08_2"))
    )
    (comp (ref "R97")
      (value "10R")
      (footprint "R0805")
      (description "Tr? 0805 1%")
      (fields (field (name "PUBLISHER") "Altium Limited"))
      (libsource (lib "") (part "RES_08_1"))
    )
    (comp (ref "R99")
      (value "10K")
      (footprint "R0805")
      (description "Tr? 0805 1%")
      (fields (field (name "PUBLISHER") "Altium Limited"))
      (libsource (lib "") (part "RES_08_2"))
    )
    (comp (ref "R101")
      (value "10R")
      (footprint "R0805")
      (description "Tr? 0805 1%")
      (fields (field (name "PUBLISHER") "Altium Limited"))
      (libsource (lib "") (part "RES_08_1"))
    )
    (comp (ref "R103")
      (value "10K")
      (footprint "R0805")
      (description "Tr? 0805 1%")
      (fields (field (name "PUBLISHER") "Altium Limited"))
      (libsource (lib "") (part "RES_08_2"))
    )
    (comp (ref "R106")
      (value "10R")
      (footprint "R0805")
      (description "Tr? 0805 1%")
      (fields (field (name "PUBLISHER") "Altium Limited"))
      (libsource (lib "") (part "RES_08_1"))
    )
    (comp (ref "R108")
      (value "1K")
      (footprint "R0805")
      (description "Tr? 0805 1%")
      (fields (field (name "PUBLISHER") "Altium Limited"))
      (libsource (lib "Schematic") (part "RES_08"))
    )
    (comp (ref "RS")
      (value "SW")
      (footprint "SW1-SMD")
      (description "Switch button 2 pin")
      (libsource (lib "TechMT.VN_Lib_Project v2") (part "SW2"))
    )
    (comp (ref "SW1")
      (value "SW")
      (footprint "SW2-DIP")
      (description "Switch button 4 pin")
      (libsource (lib "TechMT.VN_Lib_Project v2") (part "SW4"))
    )
    (comp (ref "SW2")
      (value "SW")
      (footprint "SW2-DIP")
      (description "Switch button 4 pin")
      (libsource (lib "TechMT.VN_Lib_Project v2") (part "SW4"))
    )
    (comp (ref "U1")
      (value "74HC595")
      (footprint "74HC595")
      (libsource (lib "TDX_Local_LIbrary") (part "74HC595"))
    )
    (comp (ref "U2")
      (value "74HC595")
      (footprint "74HC595")
      (libsource (lib "TDX_Local_LIbrary") (part "74HC595"))
    )
    (comp (ref "U3")
      (value "74HC595")
      (footprint "74HC595")
      (libsource (lib "TDX_Local_LIbrary") (part "74HC595"))
    )
    (comp (ref "U4")
      (value "74HC595")
      (footprint "74HC595")
      (libsource (lib "TDX_Local_LIbrary") (part "74HC595"))
    )
    (comp (ref "U5")
      (value "XL1509")
      (footprint "SO8_N")
      (description "XL1509-5.0 SOP8 DC-DC 2A 5V")
      (libsource (lib "Sonar 2019_Ver3.0") (part "XL1509"))
    )
    (comp (ref "Uart1")
      (value "Jump 4p")
      (footprint "Jump 4p")
      (libsource (lib "TDX_Local_LIbrary") (part "Jump 4p"))
    )
  )
  (nets
    (net (code "1") (name "+5V") (class "Default")
      (node (ref "C1") (pin "1") (pinfunction "1_1") (pintype "passive"))
      (node (ref "C11") (pin "3") (pinfunction "3_3") (pintype "passive"))
      (node (ref "C12") (pin "3") (pinfunction "3_3") (pintype "passive"))
      (node (ref "C14") (pin "1") (pinfunction "1_1") (pintype "passive"))
      (node (ref "C15") (pin "2") (pinfunction "2_2") (pintype "passive"))
      (node (ref "C3") (pin "1") (pinfunction "1_1") (pintype "passive"))
      (node (ref "C5") (pin "1") (pinfunction "1_1") (pintype "passive"))
      (node (ref "C9") (pin "1") (pinfunction "1_1") (pintype "passive"))
      (node (ref "IC1") (pin "3") (pinfunction "IN_3") (pintype "passive"))
      (node (ref "L1") (pin "2") (pinfunction "2_2") (pintype "passive"))
      (node (ref "U1") (pin "10") (pinfunction "~{RST}_10") (pintype "input"))
      (node (ref "U1") (pin "16") (pinfunction "VDD_16") (pintype "power_in"))
      (node (ref "U2") (pin "10") (pinfunction "~{RST}_10") (pintype "input"))
      (node (ref "U2") (pin "16") (pinfunction "VDD_16") (pintype "power_in"))
      (node (ref "U3") (pin "10") (pinfunction "~{RST}_10") (pintype "input"))
      (node (ref "U3") (pin "16") (pinfunction "VDD_16") (pintype "power_in"))
      (node (ref "U4") (pin "10") (pinfunction "~{RST}_10") (pintype "input"))
      (node (ref "U4") (pin "16") (pinfunction "VDD_16") (pintype "power_in"))
      (node (ref "U5") (pin "3") (pinfunction "FB_3") (pintype "passive"))
    )
    (net (code "2") (name "+12") (class "Default")
      (node (ref "D1") (pin "1") (pinfunction "A_1") (pintype "passive"))
      (node (ref "J8") (pin "2") (pinfunction "2_2") (pintype "passive"))
    )
    (net (code "4") (name "/A0") (class "Default")
      (node (ref "ESP1") (pin "2") (pinfunction "ADC_2") (pintype "passive"))
      (node (ref "R58") (pin "1") (pinfunction "1_1") (pintype "passive"))
      (node (ref "R65") (pin "2") (pinfunction "2_2") (pintype "passive"))
    )
    (net (code "5") (name "/ADC") (class "Default")
      (node (ref "C17") (pin "1") (pinfunction "1_1") (pintype "passive"))
      (node (ref "H1") (pin "2") (pinfunction "2_2") (pintype "passive"))
      (node (ref "R58") (pin "2") (pinfunction "2_2") (pintype "passive"))
      (node (ref "R80") (pin "2") (pinfunction "2_2") (pintype "passive"))
    )
    (net (code "6") (name "/CLK") (class "Default")
      (node (ref "ESP1") (pin "17") (pinfunction "IO2_17") (pintype "bidirectional"))
      (node (ref "R68") (pin "1") (pinfunction "1_1") (pintype "passive"))
      (node (ref "U1") (pin "11") (pinfunction "SHCP_11") (pintype "input"))
      (node (ref "U2") (pin "11") (pinfunction "SHCP_11") (pintype "input"))
      (node (ref "U3") (pin "11") (pinfunction "SHCP_11") (pintype "input"))
      (node (ref "U4") (pin "11") (pinfunction "SHCP_11") (pintype "input"))
    )
    (net (code "7") (name "/D0") (class "Default")
      (node (ref "ESP1") (pin "4") (pinfunction "IO16_4") (pintype "bidirectional"))
    )
    (net (code "8") (name "/D1") (class "Default")
      (node (ref "C12") (pin "2") (pinfunction "2_2") (pintype "passive"))
      (node (ref "ESP1") (pin "20") (pinfunction "IO5_20") (pintype "bidirectional"))
    )
    (net (code "9") (name "/D2") (class "Default")
      (node (ref "C11") (pin "2") (pinfunction "2_2") (pintype "passive"))
      (node (ref "ESP1") (pin "19") (pinfunction "IO4_19") (pintype "bidirectional"))
    )
    (net (code "10") (name "/D3") (class "Default")
      (node (ref "ESP1") (pin "18") (pinfunction "IO0_18") (pintype "bidirectional"))
      (node (ref "Flash") (pin "2") (pinfunction "2_2") (pintype "passive"))
      (node (ref "R62") (pin "1") (pinfunction "1_1") (pintype "passive"))
      (node (ref "U1") (pin "12") (pinfunction "STCP_12") (pintype "input"))
      (node (ref "U2") (pin "12") (pinfunction "STCP_12") (pintype "input"))
      (node (ref "U3") (pin "12") (pinfunction "STCP_12") (pintype "input"))
      (node (ref "U4") (pin "12") (pinfunction "STCP_12") (pintype "input"))
    )
    (net (code "11") (name "/D5") (class "Default")
      (node (ref "ESP1") (pin "5") (pinfunction "IO14_5") (pintype "bidirectional"))
      (node (ref "SW2") (pin "3") (pinfunction "3_3") (pintype "passive"))
    )
    (net (code "12") (name "/D6") (class "Default")
      (node (ref "ESP1") (pin "6") (pinfunction "IO12_6") (pintype "bidirectional"))
      (node (ref "SW1") (pin "2") (pinfunction "2_2") (pintype "passive"))
    )
    (net (code "13") (name "/D7") (class "Default")
      (node (ref "ESP1") (pin "7") (pinfunction "IO13_7") (pintype "bidirectional"))
      (node (ref "U1") (pin "14") (pinfunction "DS_14") (pintype "input"))
    )
    (net (code "14") (name "/D8") (class "Default")
      (node (ref "ESP1") (pin "16") (pinfunction "IO15_16") (pintype "bidirectional"))
      (node (ref "R69") (pin "2") (pinfunction "2_2") (pintype "passive"))
    )
    (net (code "15") (name "/EN") (class "Default")
      (node (ref "ESP1") (pin "3") (pinfunction "EN_3") (pintype "input"))
      (node (ref "R57") (pin "1") (pinfunction "1_1") (pintype "passive"))
    )
    (net (code "16") (name "/O0_HC") (class "Default")
      (node (ref "R21") (pin "1") (pinfunction "1_1") (pintype "passive"))
      (node (ref "R3") (pin "2") (pinfunction "2_2") (pintype "passive"))
      (node (ref "U1") (pin "15") (pinfunction "QA_15") (pintype "tri_state"))
    )
    (net (code "17") (name "/O1_HC") (class "Default")
      (node (ref "R20") (pin "1") (pinfunction "1_1") (pintype "passive"))
      (node (ref "R8") (pin "2") (pinfunction "2_2") (pintype "passive"))
      (node (ref "U1") (pin "1") (pinfunction "QB_1") (pintype "tri_state"))
    )
    (net (code "18") (name "/O2_HC") (class "Default")
      (node (ref "R12") (pin "2") (pinfunction "2_2") (pintype "passive"))
      (node (ref "R19") (pin "1") (pinfunction "1_1") (pintype "passive"))
      (node (ref "U1") (pin "2") (pinfunction "QC_2") (pintype "tri_state"))
    )
    (net (code "19") (name "/O3_HC") (class "Default")
      (node (ref "R18") (pin "1") (pinfunction "1_1") (pintype "passive"))
      (node (ref "R32") (pin "2") (pinfunction "2_2") (pintype "passive"))
      (node (ref "U1") (pin "3") (pinfunction "QD_3") (pintype "tri_state"))
    )
    (net (code "20") (name "/O4_HC") (class "Default")
      (node (ref "R17") (pin "1") (pinfunction "1_1") (pintype "passive"))
      (node (ref "R36") (pin "2") (pinfunction "2_2") (pintype "passive"))
      (node (ref "U1") (pin "4") (pinfunction "QE_4") (pintype "tri_state"))
    )
    (net (code "21") (name "/O5_HC") (class "Default")
      (node (ref "R16") (pin "1") (pinfunction "1_1") (pintype "passive"))
      (node (ref "R40") (pin "2") (pinfunction "2_2") (pintype "passive"))
      (node (ref "U1") (pin "5") (pinfunction "QF_5") (pintype "tri_state"))
    )
    (net (code "22") (name "/O6_HC") (class "Default")
      (node (ref "R15") (pin "1") (pinfunction "1_1") (pintype "passive"))
      (node (ref "R45") (pin "2") (pinfunction "2_2") (pintype "passive"))
      (node (ref "U1") (pin "6") (pinfunction "QG_6") (pintype "tri_state"))
    )
    (net (code "23") (name "/O7_HC") (class "Default")
      (node (ref "R14") (pin "1") (pinfunction "1_1") (pintype "passive"))
      (node (ref "R49") (pin "2") (pinfunction "2_2") (pintype "passive"))
      (node (ref "U1") (pin "7") (pinfunction "QH_7") (pintype "tri_state"))
    )
    (net (code "24") (name "/O8_HC") (class "Default")
      (node (ref "R54") (pin "2") (pinfunction "2_2") (pintype "passive"))
      (node (ref "R78") (pin "1") (pinfunction "1_1") (pintype "passive"))
      (node (ref "U2") (pin "15") (pinfunction "QA_15") (pintype "tri_state"))
    )
    (net (code "25") (name "/O9_HC") (class "Default")
      (node (ref "R60") (pin "2") (pinfunction "2_2") (pintype "passive"))
      (node (ref "R77") (pin "1") (pinfunction "1_1") (pintype "passive"))
      (node (ref "U2") (pin "1") (pinfunction "QB_1") (pintype "tri_state"))
    )
    (net (code "26") (name "/O10_HC") (class "Default")
      (node (ref "R67") (pin "2") (pinfunction "2_2") (pintype "passive"))
      (node (ref "R76") (pin "1") (pinfunction "1_1") (pintype "passive"))
      (node (ref "U2") (pin "2") (pinfunction "QC_2") (pintype "tri_state"))
    )
    (net (code "27") (name "/O11_HC") (class "Default")
      (node (ref "R75") (pin "1") (pinfunction "1_1") (pintype "passive"))
      (node (ref "R89") (pin "2") (pinfunction "2_2") (pintype "passive"))
      (node (ref "U2") (pin "3") (pinfunction "QD_3") (pintype "tri_state"))
    )
    (net (code "28") (name "/O12_HC") (class "Default")
      (node (ref "R74") (pin "1") (pinfunction "1_1") (pintype "passive"))
      (node (ref "R93") (pin "2") (pinfunction "2_2") (pintype "passive"))
      (node (ref "U2") (pin "4") (pinfunction "QE_4") (pintype "tri_state"))
    )
    (net (code "29") (name "/O13_HC") (class "Default")
      (node (ref "R73") (pin "1") (pinfunction "1_1") (pintype "passive"))
      (node (ref "R97") (pin "2") (pinfunction "2_2") (pintype "passive"))
      (node (ref "U2") (pin "5") (pinfunction "QF_5") (pintype "tri_state"))
    )
    (net (code "30") (name "/O14_HC") (class "Default")
      (node (ref "R101") (pin "2") (pinfunction "2_2") (pintype "passive"))
      (node (ref "R72") (pin "1") (pinfunction "1_1") (pintype "passive"))
      (node (ref "U2") (pin "6") (pinfunction "QG_6") (pintype "tri_state"))
    )
    (net (code "31") (name "/O15_HC") (class "Default")
      (node (ref "R106") (pin "2") (pinfunction "2_2") (pintype "passive"))
      (node (ref "R71") (pin "1") (pinfunction "1_1") (pintype "passive"))
      (node (ref "U2") (pin "7") (pinfunction "QH_7") (pintype "tri_state"))
    )
    (net (code "32") (name "/O16_HC") (class "Default")
      (node (ref "R30") (pin "1") (pinfunction "1_1") (pintype "passive"))
      (node (ref "R4") (pin "2") (pinfunction "2_2") (pintype "passive"))
      (node (ref "U3") (pin "15") (pinfunction "QA_15") (pintype "tri_state"))
    )
    (net (code "33") (name "/O17_HC") (class "Default")
      (node (ref "R29") (pin "1") (pinfunction "1_1") (pintype "passive"))
      (node (ref "R9") (pin "2") (pinfunction "2_2") (pintype "passive"))
      (node (ref "U3") (pin "1") (pinfunction "QB_1") (pintype "tri_state"))
    )
    (net (code "34") (name "/O18_HC") (class "Default")
      (node (ref "R13") (pin "2") (pinfunction "2_2") (pintype "passive"))
      (node (ref "R28") (pin "1") (pinfunction "1_1") (pintype "passive"))
      (node (ref "U3") (pin "2") (pinfunction "QC_2") (pintype "tri_state"))
    )
    (net (code "35") (name "/O19_HC") (class "Default")
      (node (ref "R27") (pin "1") (pinfunction "1_1") (pintype "passive"))
      (node (ref "R33") (pin "2") (pinfunction "2_2") (pintype "passive"))
      (node (ref "U3") (pin "3") (pinfunction "QD_3") (pintype "tri_state"))
    )
    (net (code "36") (name "/O20_HC") (class "Default")
      (node (ref "R26") (pin "1") (pinfunction "1_1") (pintype "passive"))
      (node (ref "R37") (pin "2") (pinfunction "2_2") (pintype "passive"))
      (node (ref "U3") (pin "4") (pinfunction "QE_4") (pintype "tri_state"))
    )
    (net (code "37") (name "/O21_HC") (class "Default")
      (node (ref "R25") (pin "1") (pinfunction "1_1") (pintype "passive"))
      (node (ref "R41") (pin "2") (pinfunction "2_2") (pintype "passive"))
      (node (ref "U3") (pin "5") (pinfunction "QF_5") (pintype "tri_state"))
    )
    (net (code "38") (name "/O22_HC") (class "Default")
      (node (ref "R24") (pin "1") (pinfunction "1_1") (pintype "passive"))
      (node (ref "R46") (pin "2") (pinfunction "2_2") (pintype "passive"))
      (node (ref "U3") (pin "6") (pinfunction "QG_6") (pintype "tri_state"))
    )
    (net (code "39") (name "/O23_HC") (class "Default")
      (node (ref "R23") (pin "1") (pinfunction "1_1") (pintype "passive"))
      (node (ref "R50") (pin "2") (pinfunction "2_2") (pintype "passive"))
      (node (ref "U3") (pin "7") (pinfunction "QH_7") (pintype "tri_state"))
    )
    (net (code "40") (name "/O24_HC") (class "Default")
      (node (ref "R55") (pin "2") (pinfunction "2_2") (pintype "passive"))
      (node (ref "R87") (pin "1") (pinfunction "1_1") (pintype "passive"))
      (node (ref "U4") (pin "15") (pinfunction "QA_15") (pintype "tri_state"))
    )
    (net (code "41") (name "/O25_HC") (class "Default")
      (node (ref "R61") (pin "2") (pinfunction "2_2") (pintype "passive"))
      (node (ref "R86") (pin "1") (pinfunction "1_1") (pintype "passive"))
      (node (ref "U4") (pin "1") (pinfunction "QB_1") (pintype "tri_state"))
    )
    (net (code "42") (name "/O26_HC") (class "Default")
      (node (ref "R70") (pin "2") (pinfunction "2_2") (pintype "passive"))
      (node (ref "R85") (pin "1") (pinfunction "1_1") (pintype "passive"))
      (node (ref "U4") (pin "2") (pinfunction "QC_2") (pintype "tri_state"))
    )
    (net (code "43") (name "/O27_HC") (class "Default")
      (node (ref "U4") (pin "3") (pinfunction "QD_3") (pintype "tri_state"))
    )
    (net (code "44") (name "/O28_HC") (class "Default")
      (node (ref "U4") (pin "4") (pinfunction "QE_4") (pintype "tri_state"))
    )
    (net (code "45") (name "/O29_HC") (class "Default")
      (node (ref "U4") (pin "5") (pinfunction "QF_5") (pintype "tri_state"))
    )
    (net (code "46") (name "/O30_HC") (class "Default")
      (node (ref "U4") (pin "6") (pinfunction "QG_6") (pintype "tri_state"))
    )
    (net (code "47") (name "/O31_HC") (class "Default")
      (node (ref "U4") (pin "7") (pinfunction "QH_7") (pintype "tri_state"))
    )
    (net (code "48") (name "/RS") (class "Default")
      (node (ref "ESP1") (pin "1") (pinfunction "RESET_1") (pintype "input"))
      (node (ref "R52") (pin "1") (pinfunction "1_1") (pintype "passive"))
      (node (ref "RS") (pin "2") (pinfunction "2_2") (pintype "passive"))
    )
    (net (code "49") (name "/RX") (class "Default")
      (node (ref "ESP1") (pin "21") (pinfunction "RXD_21") (pintype "input"))
      (node (ref "Uart1") (pin "4") (pinfunction "4_4") (pintype "passive"))
    )
    (net (code "50") (name "/TX") (class "Default")
      (node (ref "ESP1") (pin "22") (pinfunction "TXD_22") (pintype "output"))
      (node (ref "Uart1") (pin "3") (pinfunction "3_3") (pintype "passive"))
    )
    (net (code "51") (name "3.3V") (class "Default")
      (node (ref "C16") (pin "2") (pinfunction "2_2") (pintype "passive"))
      (node (ref "C7") (pin "2") (pinfunction "2_2") (pintype "passive"))
      (node (ref "C8") (pin "2") (pinfunction "2_2") (pintype "passive"))
      (node (ref "ESP1") (pin "8") (pinfunction "VCC_8") (pintype "power_in"))
      (node (ref "IC1") (pin "2") (pinfunction "OUT_2") (pintype "passive"))
      (node (ref "IC1") (pin "4") (pinfunction "Tab_4") (pintype "passive"))
      (node (ref "R52") (pin "2") (pinfunction "2_2") (pintype "passive"))
      (node (ref "R57") (pin "2") (pinfunction "2_2") (pintype "passive"))
      (node (ref "R62") (pin "2") (pinfunction "2_2") (pintype "passive"))
      (node (ref "R68") (pin "2") (pinfunction "2_2") (pintype "passive"))
      (node (ref "R80") (pin "1") (pinfunction "1_1") (pintype "passive"))
      (node (ref "Uart1") (pin "1") (pinfunction "1_1") (pintype "passive"))
      (node (ref "led33") (pin "1") (pinfunction "1_1") (pintype "passive"))
    )
    (net (code "52") (name "GND") (class "Default")
      (node (ref "C1") (pin "2") (pinfunction "2_2") (pintype "passive"))
      (node (ref "C11") (pin "1") (pinfunction "1_1") (pintype "passive"))
      (node (ref "C12") (pin "1") (pinfunction "1_1") (pintype "passive"))
      (node (ref "C13") (pin "1") (pinfunction "1_1") (pintype "passive"))
      (node (ref "C14") (pin "2") (pinfunction "2_2") (pintype "passive"))
      (node (ref "C15") (pin "1") (pinfunction "1_1") (pintype "passive"))
      (node (ref "C16") (pin "1") (pinfunction "1_1") (pintype "passive"))
      (node (ref "C17") (pin "2") (pinfunction "2_2") (pintype "passive"))
      (node (ref "C3") (pin "2") (pinfunction "2_2") (pintype "passive"))
      (node (ref "C5") (pin "2") (pinfunction "2_2") (pintype "passive"))
      (node (ref "C7") (pin "1") (pinfunction "1_1") (pintype "passive"))
      (node (ref "C8") (pin "1") (pinfunction "1_1") (pintype "passive"))
      (node (ref "C9") (pin "2") (pinfunction "2_2") (pintype "passive"))
      (node (ref "D2") (pin "1") (pinfunction "A_1") (pintype "passive"))
      (node (ref "ESP1") (pin "15") (pinfunction "GND_15") (pintype "power_in"))
      (node (ref "Flash") (pin "1") (pinfunction "1_1") (pintype "passive"))
      (node (ref "H1") (pin "1") (pinfunction "1_1") (pintype "passive"))
      (node (ref "IC1") (pin "1") (pinfunction "ADJ/G_1") (pintype "passive"))
      (node (ref "J8") (pin "1") (pinfunction "1_1") (pintype "passive"))
      (node (ref "Q1") (pin "3") (pinfunction "S_3") (pintype "passive"))
      (node (ref "Q10") (pin "3") (pinfunction "S_3") (pintype "passive"))
      (node (ref "Q11") (pin "3") (pinfunction "S_3") (pintype "passive"))
      (node (ref "Q12") (pin "3") (pinfunction "S_3") (pintype "passive"))
      (node (ref "Q13") (pin "3") (pinfunction "S_3") (pintype "passive"))
      (node (ref "Q14") (pin "3") (pinfunction "S_3") (pintype "passive"))
      (node (ref "Q15") (pin "3") (pinfunction "S_3") (pintype "passive"))
      (node (ref "Q16") (pin "3") (pinfunction "S_3") (pintype "passive"))
      (node (ref "Q17") (pin "3") (pinfunction "S_3") (pintype "passive"))
      (node (ref "Q18") (pin "3") (pinfunction "S_3") (pintype "passive"))
      (node (ref "Q19") (pin "3") (pinfunction "S_3") (pintype "passive"))
      (node (ref "Q2") (pin "3") (pinfunction "S_3") (pintype "passive"))
      (node (ref "Q20") (pin "3") (pinfunction "S_3") (pintype "passive"))
      (node (ref "Q21") (pin "3") (pinfunction "S_3") (pintype "passive"))
      (node (ref "Q22") (pin "3") (pinfunction "S_3") (pintype "passive"))
      (node (ref "Q23") (pin "3") (pinfunction "S_3") (pintype "passive"))
      (node (ref "Q25") (pin "3") (pinfunction "S_3") (pintype "passive"))
      (node (ref "Q27") (pin "3") (pinfunction "S_3") (pintype "passive"))
      (node (ref "Q29") (pin "3") (pinfunction "S_3") (pintype "passive"))
      (node (ref "Q3") (pin "3") (pinfunction "S_3") (pintype "passive"))
      (node (ref "Q31") (pin "3") (pinfunction "S_3") (pintype "passive"))
      (node (ref "Q4") (pin "3") (pinfunction "S_3") (pintype "passive"))
      (node (ref "Q5") (pin "3") (pinfunction "S_3") (pintype "passive"))
      (node (ref "Q6") (pin "3") (pinfunction "S_3") (pintype "passive"))
      (node (ref "Q7") (pin "3") (pinfunction "S_3") (pintype "passive"))
      (node (ref "Q8") (pin "3") (pinfunction "S_3") (pintype "passive"))
      (node (ref "Q9") (pin "3") (pinfunction "S_3") (pintype "passive"))
      (node (ref "R1") (pin "2") (pinfunction "2_2") (pintype "passive"))
      (node (ref "R10") (pin "2") (pinfunction "2_2") (pintype "passive"))
      (node (ref "R103") (pin "2") (pinfunction "2_2") (pintype "passive"))
      (node (ref "R108") (pin "2") (pinfunction "2_2") (pintype "passive"))
      (node (ref "R11") (pin "2") (pinfunction "2_2") (pintype "passive"))
      (node (ref "R2") (pin "2") (pinfunction "2_2") (pintype "passive"))
      (node (ref "R22") (pin "2") (pinfunction "2_2") (pintype "passive"))
      (node (ref "R31") (pin "2") (pinfunction "2_2") (pintype "passive"))
      (node (ref "R34") (pin "2") (pinfunction "2_2") (pintype "passive"))
      (node (ref "R35") (pin "2") (pinfunction "2_2") (pintype "passive"))
      (node (ref "R38") (pin "2") (pinfunction "2_2") (pintype "passive"))
      (node (ref "R39") (pin "2") (pinfunction "2_2") (pintype "passive"))
      (node (ref "R43") (pin "2") (pinfunction "2_2") (pintype "passive"))
      (node (ref "R44") (pin "2") (pinfunction "2_2") (pintype "passive"))
      (node (ref "R47") (pin "2") (pinfunction "2_2") (pintype "passive"))
      (node (ref "R48") (pin "2") (pinfunction "2_2") (pintype "passive"))
      (node (ref "R51") (pin "2") (pinfunction "2_2") (pintype "passive"))
      (node (ref "R53") (pin "2") (pinfunction "2_2") (pintype "passive"))
      (node (ref "R56") (pin "2") (pinfunction "2_2") (pintype "passive"))
      (node (ref "R59") (pin "2") (pinfunction "2_2") (pintype "passive"))
      (node (ref "R6") (pin "2") (pinfunction "2_2") (pintype "passive"))
      (node (ref "R64") (pin "2") (pinfunction "2_2") (pintype "passive"))
      (node (ref "R65") (pin "1") (pinfunction "1_1") (pintype "passive"))
      (node (ref "R66") (pin "2") (pinfunction "2_2") (pintype "passive"))
      (node (ref "R69") (pin "1") (pinfunction "1_1") (pintype "passive"))
      (node (ref "R7") (pin "2") (pinfunction "2_2") (pintype "passive"))
      (node (ref "R79") (pin "2") (pinfunction "2_2") (pintype "passive"))
      (node (ref "R91") (pin "2") (pinfunction "2_2") (pintype "passive"))
      (node (ref "R95") (pin "2") (pinfunction "2_2") (pintype "passive"))
      (node (ref "R99") (pin "2") (pinfunction "2_2") (pintype "passive"))
      (node (ref "RS") (pin "1") (pinfunction "1_1") (pintype "passive"))
      (node (ref "SW1") (pin "1") (pintype "passive"))
      (node (ref "SW2") (pin "1") (pintype "passive"))
      (node (ref "U1") (pin "13") (pinfunction "~{OE}_13") (pintype "input"))
      (node (ref "U1") (pin "8") (pinfunction "GND_8") (pintype "power_in"))
      (node (ref "U2") (pin "13") (pinfunction "~{OE}_13") (pintype "input"))
      (node (ref "U2") (pin "8") (pinfunction "GND_8") (pintype "power_in"))
      (node (ref "U3") (pin "13") (pinfunction "~{OE}_13") (pintype "input"))
      (node (ref "U3") (pin "8") (pinfunction "GND_8") (pintype "power_in"))
      (node (ref "U4") (pin "13") (pinfunction "~{OE}_13") (pintype "input"))
      (node (ref "U4") (pin "8") (pinfunction "GND_8") (pintype "power_in"))
      (node (ref "U5") (pin "4") (pinfunction "On/Off_4") (pintype "passive"))
      (node (ref "U5") (pin "5") (pinfunction "GND_5") (pintype "passive"))
      (node (ref "U5") (pin "6") (pinfunction "GND_6") (pintype "passive"))
      (node (ref "U5") (pin "7") (pinfunction "GND_7") (pintype "passive"))
      (node (ref "U5") (pin "8") (pinfunction "GND_8") (pintype "passive"))
      (node (ref "Uart1") (pin "2") (pinfunction "2_2") (pintype "passive"))
      (node (ref "led1") (pin "2") (pinfunction "2_2") (pintype "passive"))
      (node (ref "led10") (pin "2") (pinfunction "2_2") (pintype "passive"))
      (node (ref "led11") (pin "2") (pinfunction "2_2") (pintype "passive"))
      (node (ref "led12") (pin "2") (pinfunction "2_2") (pintype "passive"))
      (node (ref "led13") (pin "2") (pinfunction "2_2") (pintype "passive"))
      (node (ref "led14") (pin "2") (pinfunction "2_2") (pintype "passive"))
      (node (ref "led15") (pin "2") (pinfunction "2_2") (pintype "passive"))
      (node (ref "led16") (pin "2") (pinfunction "2_2") (pintype "passive"))
      (node (ref "led17") (pin "2") (pinfunction "2_2") (pintype "passive"))
      (node (ref "led18") (pin "2") (pinfunction "2_2") (pintype "passive"))
      (node (ref "led19") (pin "2") (pinfunction "2_2") (pintype "passive"))
      (node (ref "led2") (pin "2") (pinfunction "2_2") (pintype "passive"))
      (node (ref "led20") (pin "2") (pinfunction "2_2") (pintype "passive"))
      (node (ref "led21") (pin "2") (pinfunction "2_2") (pintype "passive"))
      (node (ref "led22") (pin "2") (pinfunction "2_2") (pintype "passive"))
      (node (ref "led23") (pin "2") (pinfunction "2_2") (pintype "passive"))
      (node (ref "led24") (pin "2") (pinfunction "2_2") (pintype "passive"))
      (node (ref "led3") (pin "2") (pinfunction "2_2") (pintype "passive"))
      (node (ref "led30") (pin "2") (pinfunction "2_2") (pintype "passive"))
      (node (ref "led31") (pin "2") (pinfunction "2_2") (pintype "passive"))
      (node (ref "led32") (pin "2") (pinfunction "2_2") (pintype "passive"))
      (node (ref "led4") (pin "2") (pinfunction "2_2") (pintype "passive"))
      (node (ref "led5") (pin "2") (pinfunction "2_2") (pintype "passive"))
      (node (ref "led6") (pin "2") (pinfunction "2_2") (pintype "passive"))
      (node (ref "led7") (pin "2") (pinfunction "2_2") (pintype "passive"))
      (node (ref "led8") (pin "2") (pinfunction "2_2") (pintype "passive"))
      (node (ref "led9") (pin "2") (pinfunction "2_2") (pintype "passive"))
    )
    (net (code "53") (name "Net-(D2-K)") (class "Default")
      (node (ref "D2") (pin "2") (pinfunction "K_2") (pintype "passive"))
      (node (ref "L1") (pin "1") (pinfunction "1_1") (pintype "passive"))
      (node (ref "U5") (pin "2") (pinfunction "Vout_2") (pintype "passive"))
    )
    (net (code "54") (name "Net-(Q1-D)") (class "Default")
      (node (ref "J1") (pin "1") (pinfunction "1_1") (pintype "passive"))
      (node (ref "Q1") (pin "4") (pinfunction "D_4") (pintype "passive"))
    )
    (net (code "55") (name "Net-(Q1-G)") (class "Default")
      (node (ref "Q1") (pin "1") (pinfunction "G_1") (pintype "passive"))
      (node (ref "R1") (pin "1") (pinfunction "1_1") (pintype "passive"))
      (node (ref "R3") (pin "1") (pinfunction "1_1") (pintype "passive"))
    )
    (net (code "56") (name "Net-(Q2-D)") (class "Default")
      (node (ref "J2") (pin "1") (pinfunction "1_1") (pintype "passive"))
      (node (ref "Q2") (pin "4") (pinfunction "D_4") (pintype "passive"))
    )
    (net (code "57") (name "Net-(Q2-G)") (class "Default")
      (node (ref "Q2") (pin "1") (pinfunction "G_1") (pintype "passive"))
      (node (ref "R2") (pin "1") (pinfunction "1_1") (pintype "passive"))
      (node (ref "R4") (pin "1") (pinfunction "1_1") (pintype "passive"))
    )
    (net (code "58") (name "Net-(Q3-D)") (class "Default")
      (node (ref "J1") (pin "2") (pinfunction "2_2") (pintype "passive"))
      (node (ref "Q3") (pin "4") (pinfunction "D_4") (pintype "passive"))
    )
    (net (code "59") (name "Net-(Q3-G)") (class "Default")
      (node (ref "Q3") (pin "1") (pinfunction "G_1") (pintype "passive"))
      (node (ref "R6") (pin "1") (pinfunction "1_1") (pintype "passive"))
      (node (ref "R8") (pin "1") (pinfunction "1_1") (pintype "passive"))
    )
    (net (code "60") (name "Net-(Q4-D)") (class "Default")
      (node (ref "J2") (pin "2") (pinfunction "2_2") (pintype "passive"))
      (node (ref "Q4") (pin "4") (pinfunction "D_4") (pintype "passive"))
    )
    (net (code "61") (name "Net-(Q4-G)") (class "Default")
      (node (ref "Q4") (pin "1") (pinfunction "G_1") (pintype "passive"))
      (node (ref "R7") (pin "1") (pinfunction "1_1") (pintype "passive"))
      (node (ref "R9") (pin "1") (pinfunction "1_1") (pintype "passive"))
    )
    (net (code "62") (name "Net-(Q5-D)") (class "Default")
      (node (ref "J1") (pin "3") (pinfunction "3_3") (pintype "passive"))
      (node (ref "Q5") (pin "4") (pinfunction "D_4") (pintype "passive"))
    )
    (net (code "63") (name "Net-(Q5-G)") (class "Default")
      (node (ref "Q5") (pin "1") (pinfunction "G_1") (pintype "passive"))
      (node (ref "R10") (pin "1") (pinfunction "1_1") (pintype "passive"))
      (node (ref "R12") (pin "1") (pinfunction "1_1") (pintype "passive"))
    )
    (net (code "64") (name "Net-(Q6-D)") (class "Default")
      (node (ref "J2") (pin "3") (pinfunction "3_3") (pintype "passive"))
      (node (ref "Q6") (pin "4") (pinfunction "D_4") (pintype "passive"))
    )
    (net (code "65") (name "Net-(Q6-G)") (class "Default")
      (node (ref "Q6") (pin "1") (pinfunction "G_1") (pintype "passive"))
      (node (ref "R11") (pin "1") (pinfunction "1_1") (pintype "passive"))
      (node (ref "R13") (pin "1") (pinfunction "1_1") (pintype "passive"))
    )
    (net (code "66") (name "Net-(Q7-D)") (class "Default")
      (node (ref "J1") (pin "4") (pinfunction "4_4") (pintype "passive"))
      (node (ref "Q7") (pin "4") (pinfunction "D_4") (pintype "passive"))
    )
    (net (code "67") (name "Net-(Q7-G)") (class "Default")
      (node (ref "Q7") (pin "1") (pinfunction "G_1") (pintype "passive"))
      (node (ref "R22") (pin "1") (pinfunction "1_1") (pintype "passive"))
      (node (ref "R32") (pin "1") (pinfunction "1_1") (pintype "passive"))
    )
    (net (code "68") (name "Net-(Q8-D)") (class "Default")
      (node (ref "J2") (pin "4") (pinfunction "4_4") (pintype "passive"))
      (node (ref "Q8") (pin "4") (pinfunction "D_4") (pintype "passive"))
    )
    (net (code "69") (name "Net-(Q8-G)") (class "Default")
      (node (ref "Q8") (pin "1") (pinfunction "G_1") (pintype "passive"))
      (node (ref "R31") (pin "1") (pinfunction "1_1") (pintype "passive"))
      (node (ref "R33") (pin "1") (pinfunction "1_1") (pintype "passive"))
    )
    (net (code "70") (name "Net-(Q9-D)") (class "Default")
      (node (ref "J3") (pin "1") (pinfunction "1_1") (pintype "passive"))
      (node (ref "Q9") (pin "4") (pinfunction "D_4") (pintype "passive"))
    )
    (net (code "71") (name "Net-(Q9-G)") (class "Default")
      (node (ref "Q9") (pin "1") (pinfunction "G_1") (pintype "passive"))
      (node (ref "R34") (pin "1") (pinfunction "1_1") (pintype "passive"))
      (node (ref "R36") (pin "1") (pinfunction "1_1") (pintype "passive"))
    )
    (net (code "72") (name "Net-(Q10-D)") (class "Default")
      (node (ref "J4") (pin "1") (pinfunction "1_1") (pintype "passive"))
      (node (ref "Q10") (pin "4") (pinfunction "D_4") (pintype "passive"))
    )
    (net (code "73") (name "Net-(Q10-G)") (class "Default")
      (node (ref "Q10") (pin "1") (pinfunction "G_1") (pintype "passive"))
      (node (ref "R35") (pin "1") (pinfunction "1_1") (pintype "passive"))
      (node (ref "R37") (pin "1") (pinfunction "1_1") (pintype "passive"))
    )
    (net (code "74") (name "Net-(Q11-D)") (class "Default")
      (node (ref "J3") (pin "2") (pinfunction "2_2") (pintype "passive"))
      (node (ref "Q11") (pin "4") (pinfunction "D_4") (pintype "passive"))
    )
    (net (code "75") (name "Net-(Q11-G)") (class "Default")
      (node (ref "Q11") (pin "1") (pinfunction "G_1") (pintype "passive"))
      (node (ref "R38") (pin "1") (pinfunction "1_1") (pintype "passive"))
      (node (ref "R40") (pin "1") (pinfunction "1_1") (pintype "passive"))
    )
    (net (code "76") (name "Net-(Q12-D)") (class "Default")
      (node (ref "J4") (pin "2") (pinfunction "2_2") (pintype "passive"))
      (node (ref "Q12") (pin "4") (pinfunction "D_4") (pintype "passive"))
    )
    (net (code "77") (name "Net-(Q12-G)") (class "Default")
      (node (ref "Q12") (pin "1") (pinfunction "G_1") (pintype "passive"))
      (node (ref "R39") (pin "1") (pinfunction "1_1") (pintype "passive"))
      (node (ref "R41") (pin "1") (pinfunction "1_1") (pintype "passive"))
    )
    (net (code "78") (name "Net-(Q13-D)") (class "Default")
      (node (ref "J3") (pin "3") (pinfunction "3_3") (pintype "passive"))
      (node (ref "Q13") (pin "4") (pinfunction "D_4") (pintype "passive"))
    )
    (net (code "79") (name "Net-(Q13-G)") (class "Default")
      (node (ref "Q13") (pin "1") (pinfunction "G_1") (pintype "passive"))
      (node (ref "R43") (pin "1") (pinfunction "1_1") (pintype "passive"))
      (node (ref "R45") (pin "1") (pinfunction "1_1") (pintype "passive"))
    )
    (net (code "80") (name "Net-(Q14-D)") (class "Default")
      (node (ref "J4") (pin "3") (pinfunction "3_3") (pintype "passive"))
      (node (ref "Q14") (pin "4") (pinfunction "D_4") (pintype "passive"))
    )
    (net (code "81") (name "Net-(Q14-G)") (class "Default")
      (node (ref "Q14") (pin "1") (pinfunction "G_1") (pintype "passive"))
      (node (ref "R44") (pin "1") (pinfunction "1_1") (pintype "passive"))
      (node (ref "R46") (pin "1") (pinfunction "1_1") (pintype "passive"))
    )
    (net (code "82") (name "Net-(Q15-D)") (class "Default")
      (node (ref "J3") (pin "4") (pinfunction "4_4") (pintype "passive"))
      (node (ref "Q15") (pin "4") (pinfunction "D_4") (pintype "passive"))
    )
    (net (code "83") (name "Net-(Q15-G)") (class "Default")
      (node (ref "Q15") (pin "1") (pinfunction "G_1") (pintype "passive"))
      (node (ref "R47") (pin "1") (pinfunction "1_1") (pintype "passive"))
      (node (ref "R49") (pin "1") (pinfunction "1_1") (pintype "passive"))
    )
    (net (code "84") (name "Net-(Q16-D)") (class "Default")
      (node (ref "J4") (pin "4") (pinfunction "4_4") (pintype "passive"))
      (node (ref "Q16") (pin "4") (pinfunction "D_4") (pintype "passive"))
    )
    (net (code "85") (name "Net-(Q16-G)") (class "Default")
      (node (ref "Q16") (pin "1") (pinfunction "G_1") (pintype "passive"))
      (node (ref "R48") (pin "1") (pinfunction "1_1") (pintype "passive"))
      (node (ref "R50") (pin "1") (pinfunction "1_1") (pintype "passive"))
    )
    (net (code "86") (name "Net-(Q17-D)") (class "Default")
      (node (ref "J5") (pin "1") (pinfunction "1_1") (pintype "passive"))
      (node (ref "Q17") (pin "4") (pinfunction "D_4") (pintype "passive"))
    )
    (net (code "87") (name "Net-(Q17-G)") (class "Default")
      (node (ref "Q17") (pin "1") (pinfunction "G_1") (pintype "passive"))
      (node (ref "R51") (pin "1") (pinfunction "1_1") (pintype "passive"))
      (node (ref "R54") (pin "1") (pinfunction "1_1") (pintype "passive"))
    )
    (net (code "88") (name "Net-(Q18-D)") (class "Default")
      (node (ref "J6") (pin "1") (pinfunction "1_1") (pintype "passive"))
      (node (ref "Q18") (pin "4") (pinfunction "D_4") (pintype "passive"))
    )
    (net (code "89") (name "Net-(Q18-G)") (class "Default")
      (node (ref "Q18") (pin "1") (pinfunction "G_1") (pintype "passive"))
      (node (ref "R53") (pin "1") (pinfunction "1_1") (pintype "passive"))
      (node (ref "R55") (pin "1") (pinfunction "1_1") (pintype "passive"))
    )
    (net (code "90") (name "Net-(Q19-D)") (class "Default")
      (node (ref "J5") (pin "2") (pinfunction "2_2") (pintype "passive"))
      (node (ref "Q19") (pin "4") (pinfunction "D_4") (pintype "passive"))
    )
    (net (code "91") (name "Net-(Q19-G)") (class "Default")
      (node (ref "Q19") (pin "1") (pinfunction "G_1") (pintype "passive"))
      (node (ref "R56") (pin "1") (pinfunction "1_1") (pintype "passive"))
      (node (ref "R60") (pin "1") (pinfunction "1_1") (pintype "passive"))
    )
    (net (code "92") (name "Net-(Q20-D)") (class "Default")
      (node (ref "J6") (pin "2") (pinfunction "2_2") (pintype "passive"))
      (node (ref "Q20") (pin "4") (pinfunction "D_4") (pintype "passive"))
    )
    (net (code "93") (name "Net-(Q20-G)") (class "Default")
      (node (ref "Q20") (pin "1") (pinfunction "G_1") (pintype "passive"))
      (node (ref "R59") (pin "1") (pinfunction "1_1") (pintype "passive"))
      (node (ref "R61") (pin "1") (pinfunction "1_1") (pintype "passive"))
    )
    (net (code "94") (name "Net-(Q21-D)") (class "Default")
      (node (ref "J5") (pin "3") (pinfunction "3_3") (pintype "passive"))
      (node (ref "Q21") (pin "4") (pinfunction "D_4") (pintype "passive"))
    )
    (net (code "95") (name "Net-(Q21-G)") (class "Default")
      (node (ref "Q21") (pin "1") (pinfunction "G_1") (pintype "passive"))
      (node (ref "R64") (pin "1") (pinfunction "1_1") (pintype "passive"))
      (node (ref "R67") (pin "1") (pinfunction "1_1") (pintype "passive"))
    )
    (net (code "96") (name "Net-(Q22-D)") (class "Default")
      (node (ref "J6") (pin "3") (pinfunction "3_3") (pintype "passive"))
      (node (ref "Q22") (pin "4") (pinfunction "D_4") (pintype "passive"))
    )
    (net (code "97") (name "Net-(Q22-G)") (class "Default")
      (node (ref "Q22") (pin "1") (pinfunction "G_1") (pintype "passive"))
      (node (ref "R66") (pin "1") (pinfunction "1_1") (pintype "passive"))
      (node (ref "R70") (pin "1") (pinfunction "1_1") (pintype "passive"))
    )
    (net (code "98") (name "Net-(Q23-D)") (class "Default")
      (node (ref "J5") (pin "4") (pinfunction "4_4") (pintype "passive"))
      (node (ref "Q23") (pin "4") (pinfunction "D_4") (pintype "passive"))
    )
    (net (code "99") (name "Net-(Q23-G)") (class "Default")
      (node (ref "Q23") (pin "1") (pinfunction "G_1") (pintype "passive"))
      (node (ref "R79") (pin "1") (pinfunction "1_1") (pintype "passive"))
      (node (ref "R89") (pin "1") (pinfunction "1_1") (pintype "passive"))
    )
    (net (code "100") (name "Net-(Q25-D)") (class "Default")
      (node (ref "J7") (pin "1") (pinfunction "1_1") (pintype "passive"))
      (node (ref "Q25") (pin "4") (pinfunction "D_4") (pintype "passive"))
    )
    (net (code "101") (name "Net-(Q25-G)") (class "Default")
      (node (ref "Q25") (pin "1") (pinfunction "G_1") (pintype "passive"))
      (node (ref "R91") (pin "1") (pinfunction "1_1") (pintype "passive"))
      (node (ref "R93") (pin "1") (pinfunction "1_1") (pintype "passive"))
    )
    (net (code "102") (name "Net-(Q27-D)") (class "Default")
      (node (ref "J7") (pin "2") (pinfunction "2_2") (pintype "passive"))
      (node (ref "Q27") (pin "4") (pinfunction "D_4") (pintype "passive"))
    )
    (net (code "103") (name "Net-(Q27-G)") (class "Default")
      (node (ref "Q27") (pin "1") (pinfunction "G_1") (pintype "passive"))
      (node (ref "R95") (pin "1") (pinfunction "1_1") (pintype "passive"))
      (node (ref "R97") (pin "1") (pinfunction "1_1") (pintype "passive"))
    )
    (net (code "104") (name "Net-(Q29-D)") (class "Default")
      (node (ref "J7") (pin "3") (pinfunction "3_3") (pintype "passive"))
      (node (ref "Q29") (pin "4") (pinfunction "D_4") (pintype "passive"))
    )
    (net (code "105") (name "Net-(Q29-G)") (class "Default")
      (node (ref "Q29") (pin "1") (pinfunction "G_1") (pintype "passive"))
      (node (ref "R101") (pin "1") (pinfunction "1_1") (pintype "passive"))
      (node (ref "R99") (pin "1") (pinfunction "1_1") (pintype "passive"))
    )
    (net (code "106") (name "Net-(Q31-D)") (class "Default")
      (node (ref "J7") (pin "4") (pinfunction "4_4") (pintype "passive"))
      (node (ref "Q31") (pin "4") (pinfunction "D_4") (pintype "passive"))
    )
    (net (code "107") (name "Net-(Q31-G)") (class "Default")
      (node (ref "Q31") (pin "1") (pinfunction "G_1") (pintype "passive"))
      (node (ref "R103") (pin "1") (pinfunction "1_1") (pintype "passive"))
      (node (ref "R106") (pin "1") (pinfunction "1_1") (pintype "passive"))
    )
    (net (code "108") (name "Net-(R14-Pad2)") (class "Default")
      (node (ref "R14") (pin "2") (pinfunction "2_2") (pintype "passive"))
      (node (ref "led1") (pin "1") (pinfunction "1_1") (pintype "passive"))
    )
    (net (code "109") (name "Net-(R15-Pad2)") (class "Default")
      (node (ref "R15") (pin "2") (pinfunction "2_2") (pintype "passive"))
      (node (ref "led2") (pin "1") (pinfunction "1_1") (pintype "passive"))
    )
    (net (code "110") (name "Net-(R16-Pad2)") (class "Default")
      (node (ref "R16") (pin "2") (pinfunction "2_2") (pintype "passive"))
      (node (ref "led3") (pin "1") (pinfunction "1_1") (pintype "passive"))
    )
    (net (code "111") (name "Net-(R17-Pad2)") (class "Default")
      (node (ref "R17") (pin "2") (pinfunction "2_2") (pintype "passive"))
      (node (ref "led4") (pin "1") (pinfunction "1_1") (pintype "passive"))
    )
    (net (code "112") (name "Net-(R18-Pad2)") (class "Default")
      (node (ref "R18") (pin "2") (pinfunction "2_2") (pintype "passive"))
      (node (ref "led5") (pin "1") (pinfunction "1_1") (pintype "passive"))
    )
    (net (code "113") (name "Net-(R19-Pad2)") (class "Default")
      (node (ref "R19") (pin "2") (pinfunction "2_2") (pintype "passive"))
      (node (ref "led6") (pin "1") (pinfunction "1_1") (pintype "passive"))
    )
    (net (code "114") (name "Net-(R20-Pad2)") (class "Default")
      (node (ref "R20") (pin "2") (pinfunction "2_2") (pintype "passive"))
      (node (ref "led7") (pin "1") (pinfunction "1_1") (pintype "passive"))
    )
    (net (code "115") (name "Net-(R21-Pad2)") (class "Default")
      (node (ref "R21") (pin "2") (pinfunction "2_2") (pintype "passive"))
      (node (ref "led8") (pin "1") (pinfunction "1_1") (pintype "passive"))
    )
    (net (code "116") (name "Net-(R23-Pad2)") (class "Default")
      (node (ref "R23") (pin "2") (pinfunction "2_2") (pintype "passive"))
      (node (ref "led9") (pin "1") (pinfunction "1_1") (pintype "passive"))
    )
    (net (code "117") (name "Net-(R24-Pad2)") (class "Default")
      (node (ref "R24") (pin "2") (pinfunction "2_2") (pintype "passive"))
      (node (ref "led10") (pin "1") (pinfunction "1_1") (pintype "passive"))
    )
    (net (code "118") (name "Net-(R25-Pad2)") (class "Default")
      (node (ref "R25") (pin "2") (pinfunction "2_2") (pintype "passive"))
      (node (ref "led11") (pin "1") (pinfunction "1_1") (pintype "passive"))
    )
    (net (code "119") (name "Net-(R26-Pad2)") (class "Default")
      (node (ref "R26") (pin "2") (pinfunction "2_2") (pintype "passive"))
      (node (ref "led12") (pin "1") (pinfunction "1_1") (pintype "passive"))
    )
    (net (code "120") (name "Net-(R27-Pad2)") (class "Default")
      (node (ref "R27") (pin "2") (pinfunction "2_2") (pintype "passive"))
      (node (ref "led13") (pin "1") (pinfunction "1_1") (pintype "passive"))
    )
    (net (code "121") (name "Net-(R28-Pad2)") (class "Default")
      (node (ref "R28") (pin "2") (pinfunction "2_2") (pintype "passive"))
      (node (ref "led14") (pin "1") (pinfunction "1_1") (pintype "passive"))
    )
    (net (code "122") (name "Net-(R29-Pad2)") (class "Default")
      (node (ref "R29") (pin "2") (pinfunction "2_2") (pintype "passive"))
      (node (ref "led15") (pin "1") (pinfunction "1_1") (pintype "passive"))
    )
    (net (code "123") (name "Net-(R30-Pad2)") (class "Default")
      (node (ref "R30") (pin "2") (pinfunction "2_2") (pintype "passive"))
      (node (ref "led16") (pin "1") (pinfunction "1_1") (pintype "passive"))
    )
    (net (code "124") (name "Net-(R71-Pad2)") (class "Default")
      (node (ref "R71") (pin "2") (pinfunction "2_2") (pintype "passive"))
      (node (ref "led17") (pin "1") (pinfunction "1_1") (pintype "passive"))
    )
    (net (code "125") (name "Net-(R72-Pad2)") (class "Default")
      (node (ref "R72") (pin "2") (pinfunction "2_2") (pintype "passive"))
      (node (ref "led18") (pin "1") (pinfunction "1_1") (pintype "passive"))
    )
    (net (code "126") (name "Net-(R73-Pad2)") (class "Default")
      (node (ref "R73") (pin "2") (pinfunction "2_2") (pintype "passive"))
      (node (ref "led19") (pin "1") (pinfunction "1_1") (pintype "passive"))
    )
    (net (code "127") (name "Net-(R74-Pad2)") (class "Default")
      (node (ref "R74") (pin "2") (pinfunction "2_2") (pintype "passive"))
      (node (ref "led20") (pin "1") (pinfunction "1_1") (pintype "passive"))
    )
    (net (code "128") (name "Net-(R75-Pad2)") (class "Default")
      (node (ref "R75") (pin "2") (pinfunction "2_2") (pintype "passive"))
      (node (ref "led21") (pin "1") (pinfunction "1_1") (pintype "passive"))
    )
    (net (code "129") (name "Net-(R76-Pad2)") (class "Default")
      (node (ref "R76") (pin "2") (pinfunction "2_2") (pintype "passive"))
      (node (ref "led22") (pin "1") (pinfunction "1_1") (pintype "passive"))
    )
    (net (code "130") (name "Net-(R77-Pad2)") (class "Default")
      (node (ref "R77") (pin "2") (pinfunction "2_2") (pintype "passive"))
      (node (ref "led23") (pin "1") (pinfunction "1_1") (pintype "passive"))
    )
    (net (code "131") (name "Net-(R78-Pad2)") (class "Default")
      (node (ref "R78") (pin "2") (pinfunction "2_2") (pintype "passive"))
      (node (ref "led24") (pin "1") (pinfunction "1_1") (pintype "passive"))
    )
    (net (code "132") (name "Net-(R85-Pad2)") (class "Default")
      (node (ref "R85") (pin "2") (pinfunction "2_2") (pintype "passive"))
      (node (ref "led30") (pin "1") (pinfunction "1_1") (pintype "passive"))
    )
    (net (code "133") (name "Net-(R86-Pad2)") (class "Default")
      (node (ref "R86") (pin "2") (pinfunction "2_2") (pintype "passive"))
      (node (ref "led31") (pin "1") (pinfunction "1_1") (pintype "passive"))
    )
    (net (code "134") (name "Net-(R87-Pad2)") (class "Default")
      (node (ref "R87") (pin "2") (pinfunction "2_2") (pintype "passive"))
      (node (ref "led32") (pin "1") (pinfunction "1_1") (pintype "passive"))
    )
    (net (code "135") (name "Net-(R108-Pad1)") (class "Default")
      (node (ref "R108") (pin "1") (pinfunction "1_1") (pintype "passive"))
      (node (ref "led33") (pin "2") (pinfunction "2_2") (pintype "passive"))
    )
    (net (code "136") (name "Net-(U1-DATAO)") (class "Default")
      (node (ref "U1") (pin "9") (pinfunction "DATAO_9") (pintype "output"))
      (node (ref "U2") (pin "14") (pinfunction "DS_14") (pintype "input"))
    )
    (net (code "137") (name "Net-(U2-DATAO)") (class "Default")
      (node (ref "U2") (pin "9") (pinfunction "DATAO_9") (pintype "output"))
      (node (ref "U3") (pin "14") (pinfunction "DS_14") (pintype "input"))
    )
    (net (code "138") (name "Net-(U3-DATAO)") (class "Default")
      (node (ref "U3") (pin "9") (pinfunction "DATAO_9") (pintype "output"))
      (node (ref "U4") (pin "14") (pinfunction "DS_14") (pintype "input"))
    )
    (net (code "139") (name "Net-(U5-Vin)") (class "Default")
      (node (ref "C13") (pin "2") (pinfunction "2_2") (pintype "passive"))
      (node (ref "F1") (pin "1") (pinfunction "1_1") (pintype "passive"))
      (node (ref "U5") (pin "1") (pinfunction "Vin_1") (pintype "passive"))
    )
    (net (code "140") (name "Vin") (class "Default")
      (node (ref "D1") (pin "2") (pinfunction "K_2") (pintype "passive"))
      (node (ref "F1") (pin "2") (pinfunction "2_2") (pintype "passive"))
    )
    (net (code "141") (name "unconnected-(ESP1-CS0-Pad9)") (class "Default")
      (node (ref "ESP1") (pin "9") (pinfunction "CS0_9") (pintype "input"))
    )
    (net (code "142") (name "unconnected-(ESP1-IO9-Pad11)") (class "Default")
      (node (ref "ESP1") (pin "11") (pinfunction "IO9_11") (pintype "bidirectional"))
    )
    (net (code "143") (name "unconnected-(ESP1-IO10-Pad12)") (class "Default")
      (node (ref "ESP1") (pin "12") (pinfunction "IO10_12") (pintype "bidirectional"))
    )
    (net (code "144") (name "unconnected-(ESP1-MISO-Pad10)") (class "Default")
      (node (ref "ESP1") (pin "10") (pinfunction "MISO_10") (pintype "bidirectional"))
    )
    (net (code "145") (name "unconnected-(ESP1-MOSI-Pad13)") (class "Default")
      (node (ref "ESP1") (pin "13") (pinfunction "MOSI_13") (pintype "bidirectional"))
    )
    (net (code "146") (name "unconnected-(ESP1-SCLK-Pad14)") (class "Default")
      (node (ref "ESP1") (pin "14") (pinfunction "SCLK_14") (pintype "input"))
    )
    (net (code "147") (name "unconnected-(J6-Pad4)") (class "Default")
      (node (ref "J6") (pin "4") (pinfunction "4_4") (pintype "passive"))
    )
    (net (code "148") (name "unconnected-(SW1-Pad3)") (class "Default")
      (node (ref "SW1") (pin "3") (pinfunction "3_3") (pintype "passive"))
    )
    (net (code "149") (name "unconnected-(SW1-Pad4)") (class "Default")
      (node (ref "SW1") (pin "4") (pinfunction "4_4") (pintype "passive"))
    )
    (net (code "150") (name "unconnected-(SW2-Pad2)") (class "Default")
      (node (ref "SW2") (pin "2") (pinfunction "2_2") (pintype "passive"))
    )
    (net (code "151") (name "unconnected-(SW2-Pad4)") (class "Default")
      (node (ref "SW2") (pin "4") (pinfunction "4_4") (pintype "passive"))
    )
    (net (code "152") (name "unconnected-(U4-DATAO-Pad9)") (class "Default")
      (node (ref "U4") (pin "9") (pinfunction "DATAO_9") (pintype "output"))
    )
  )
)
